# CESC16.net
KiCad netlist of a schematic drawn in EasyEDA
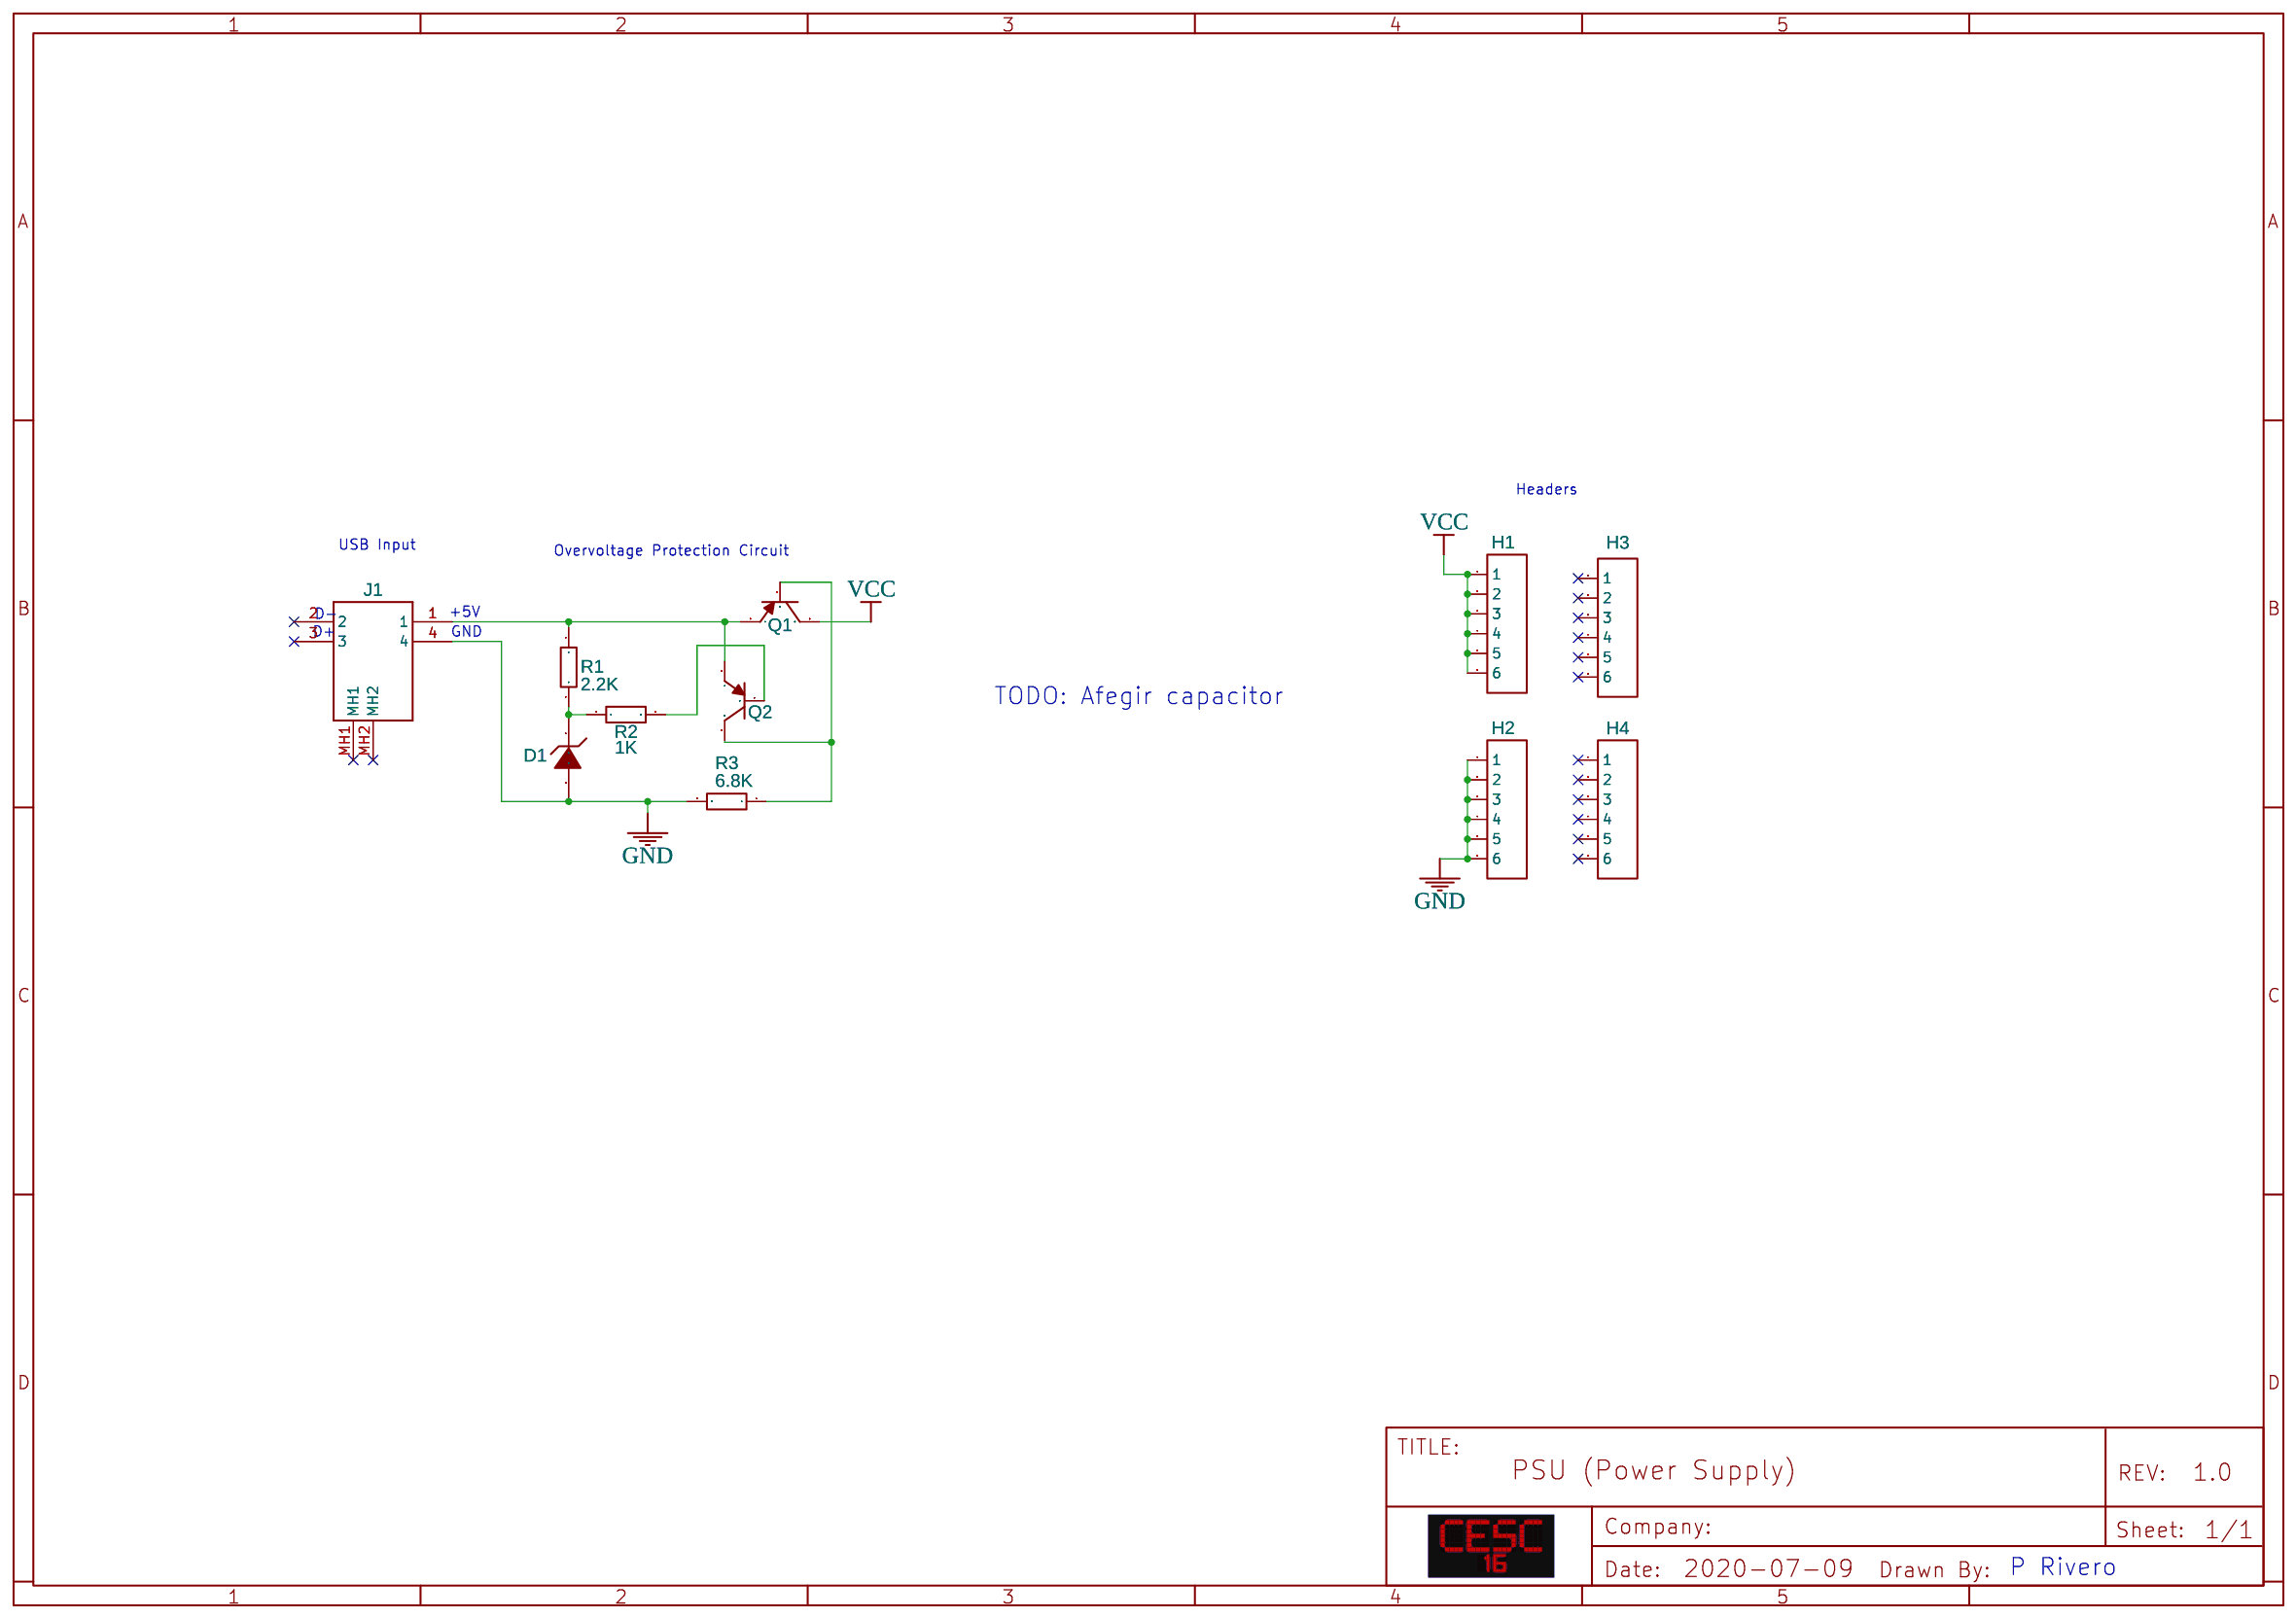
[diagram p0: PSU]
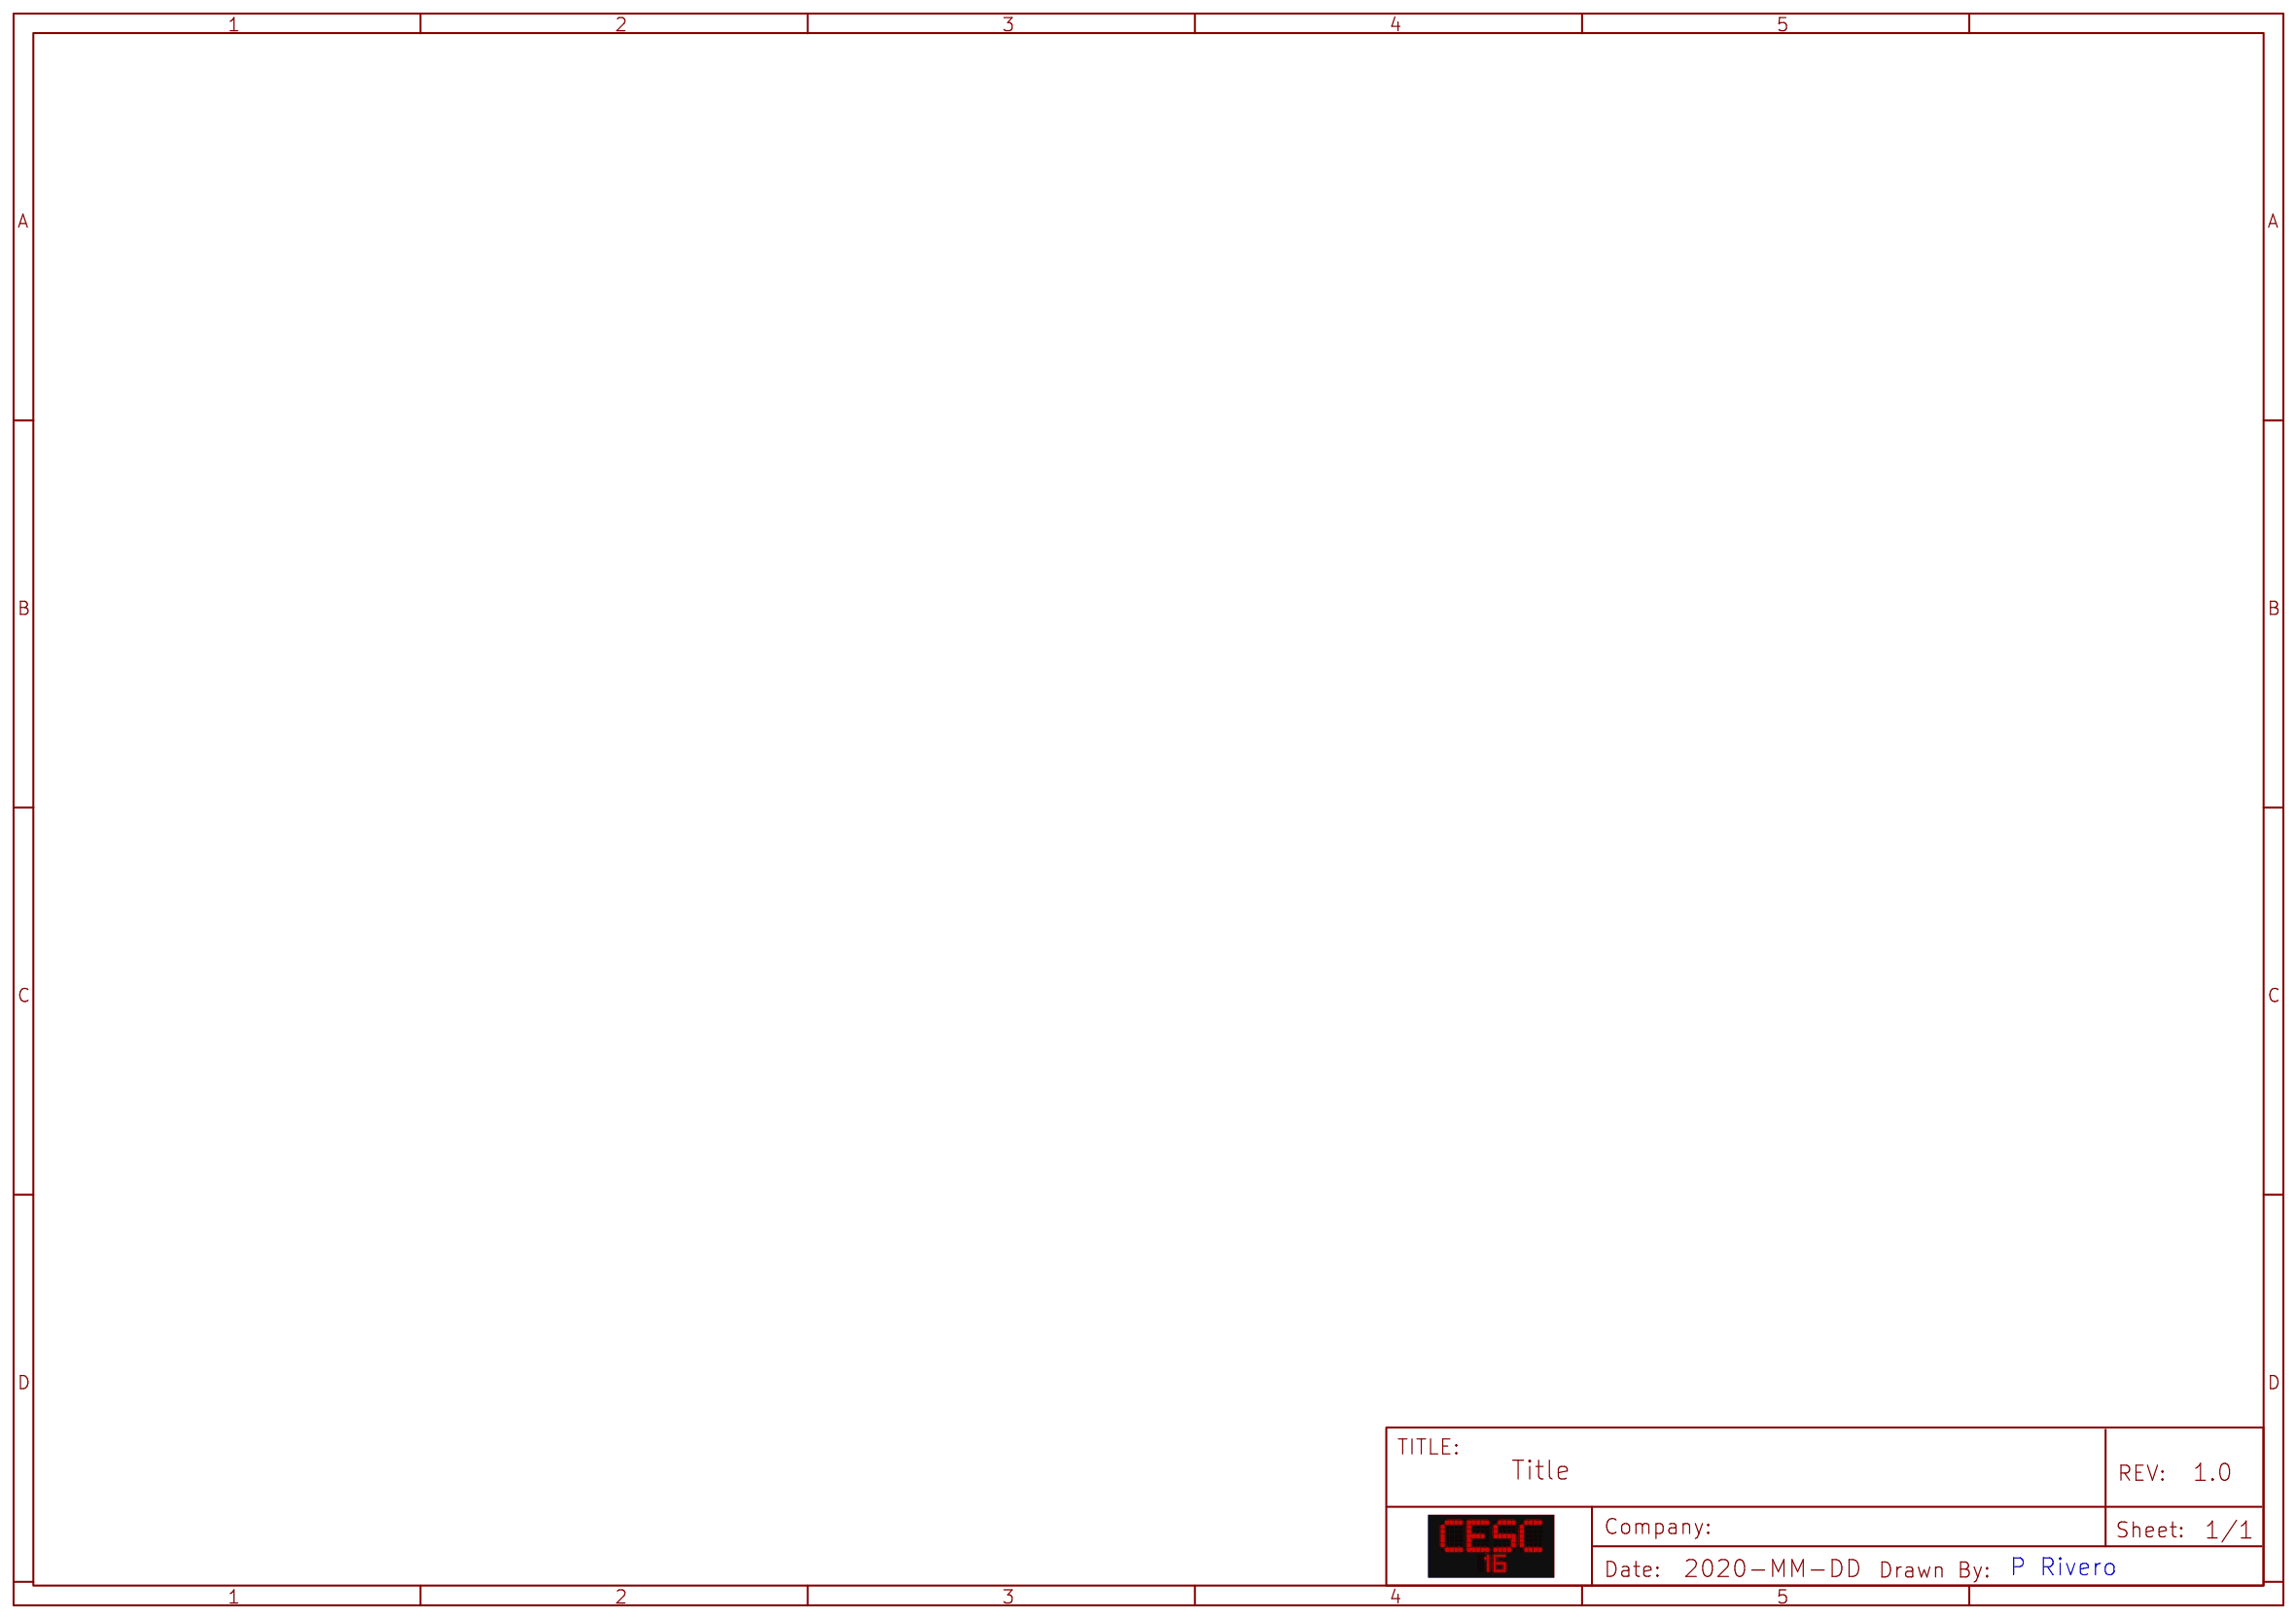
[diagram p1: _Template]
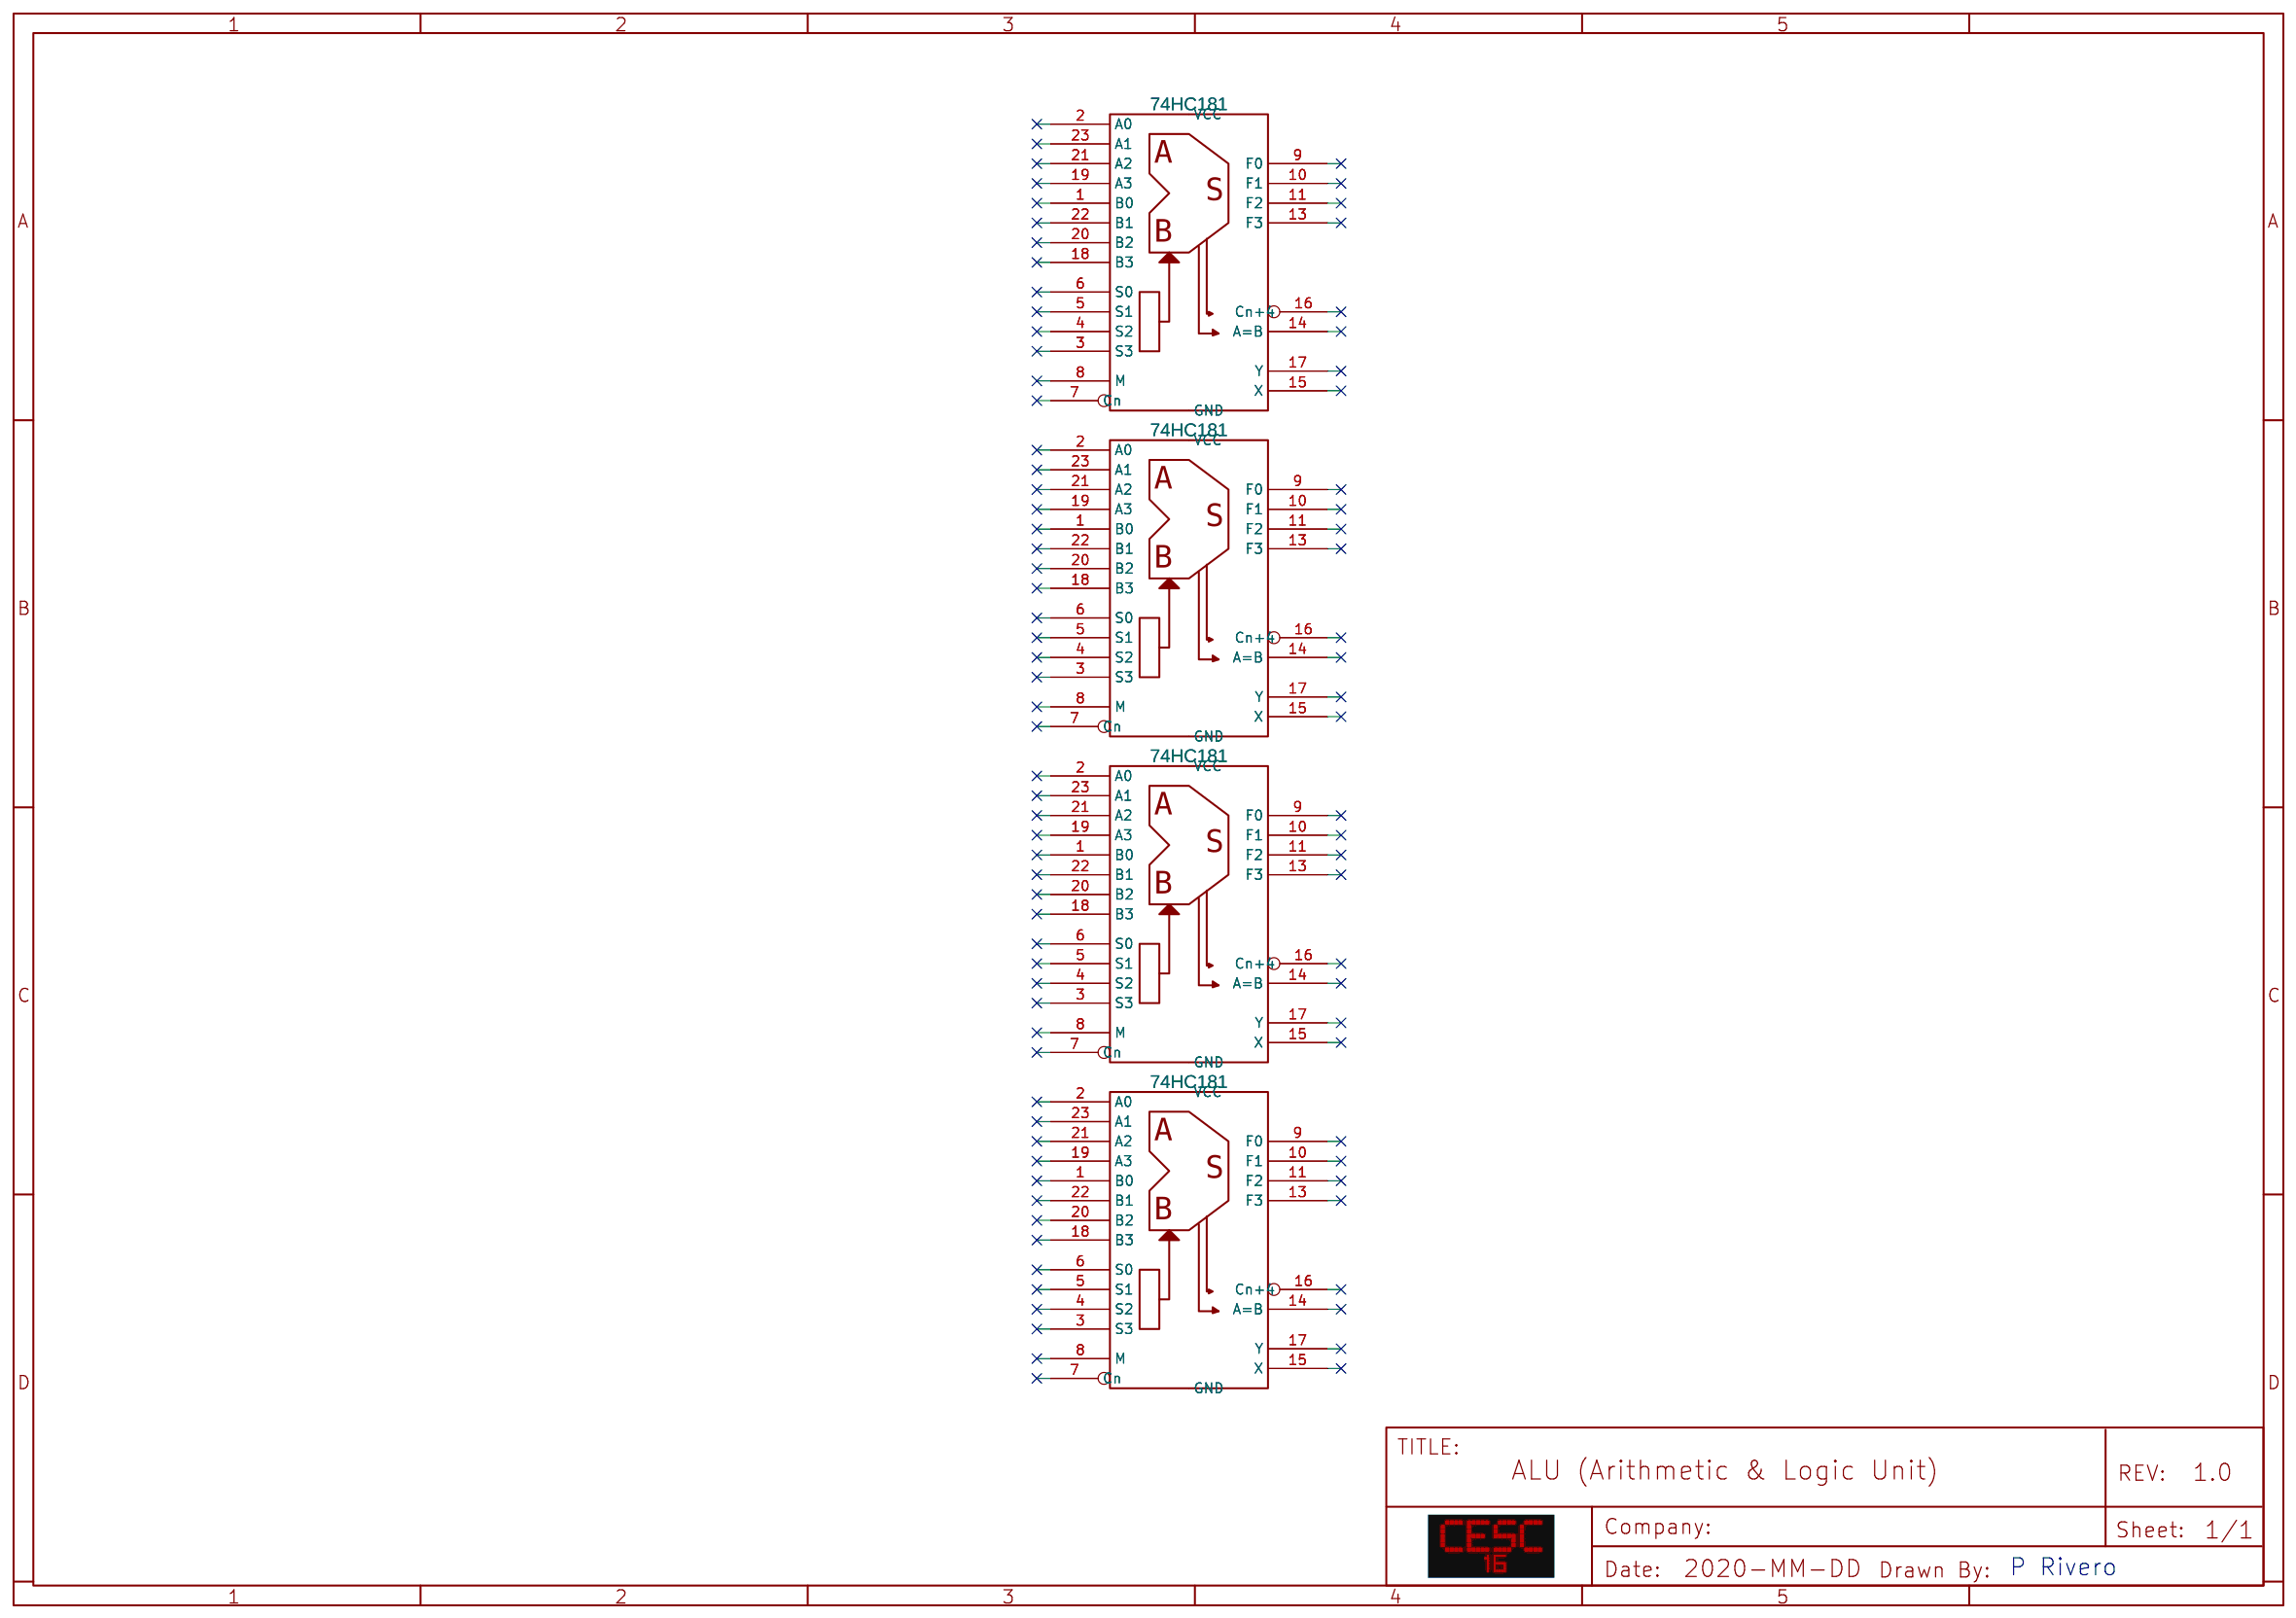
[diagram p2: ALU]
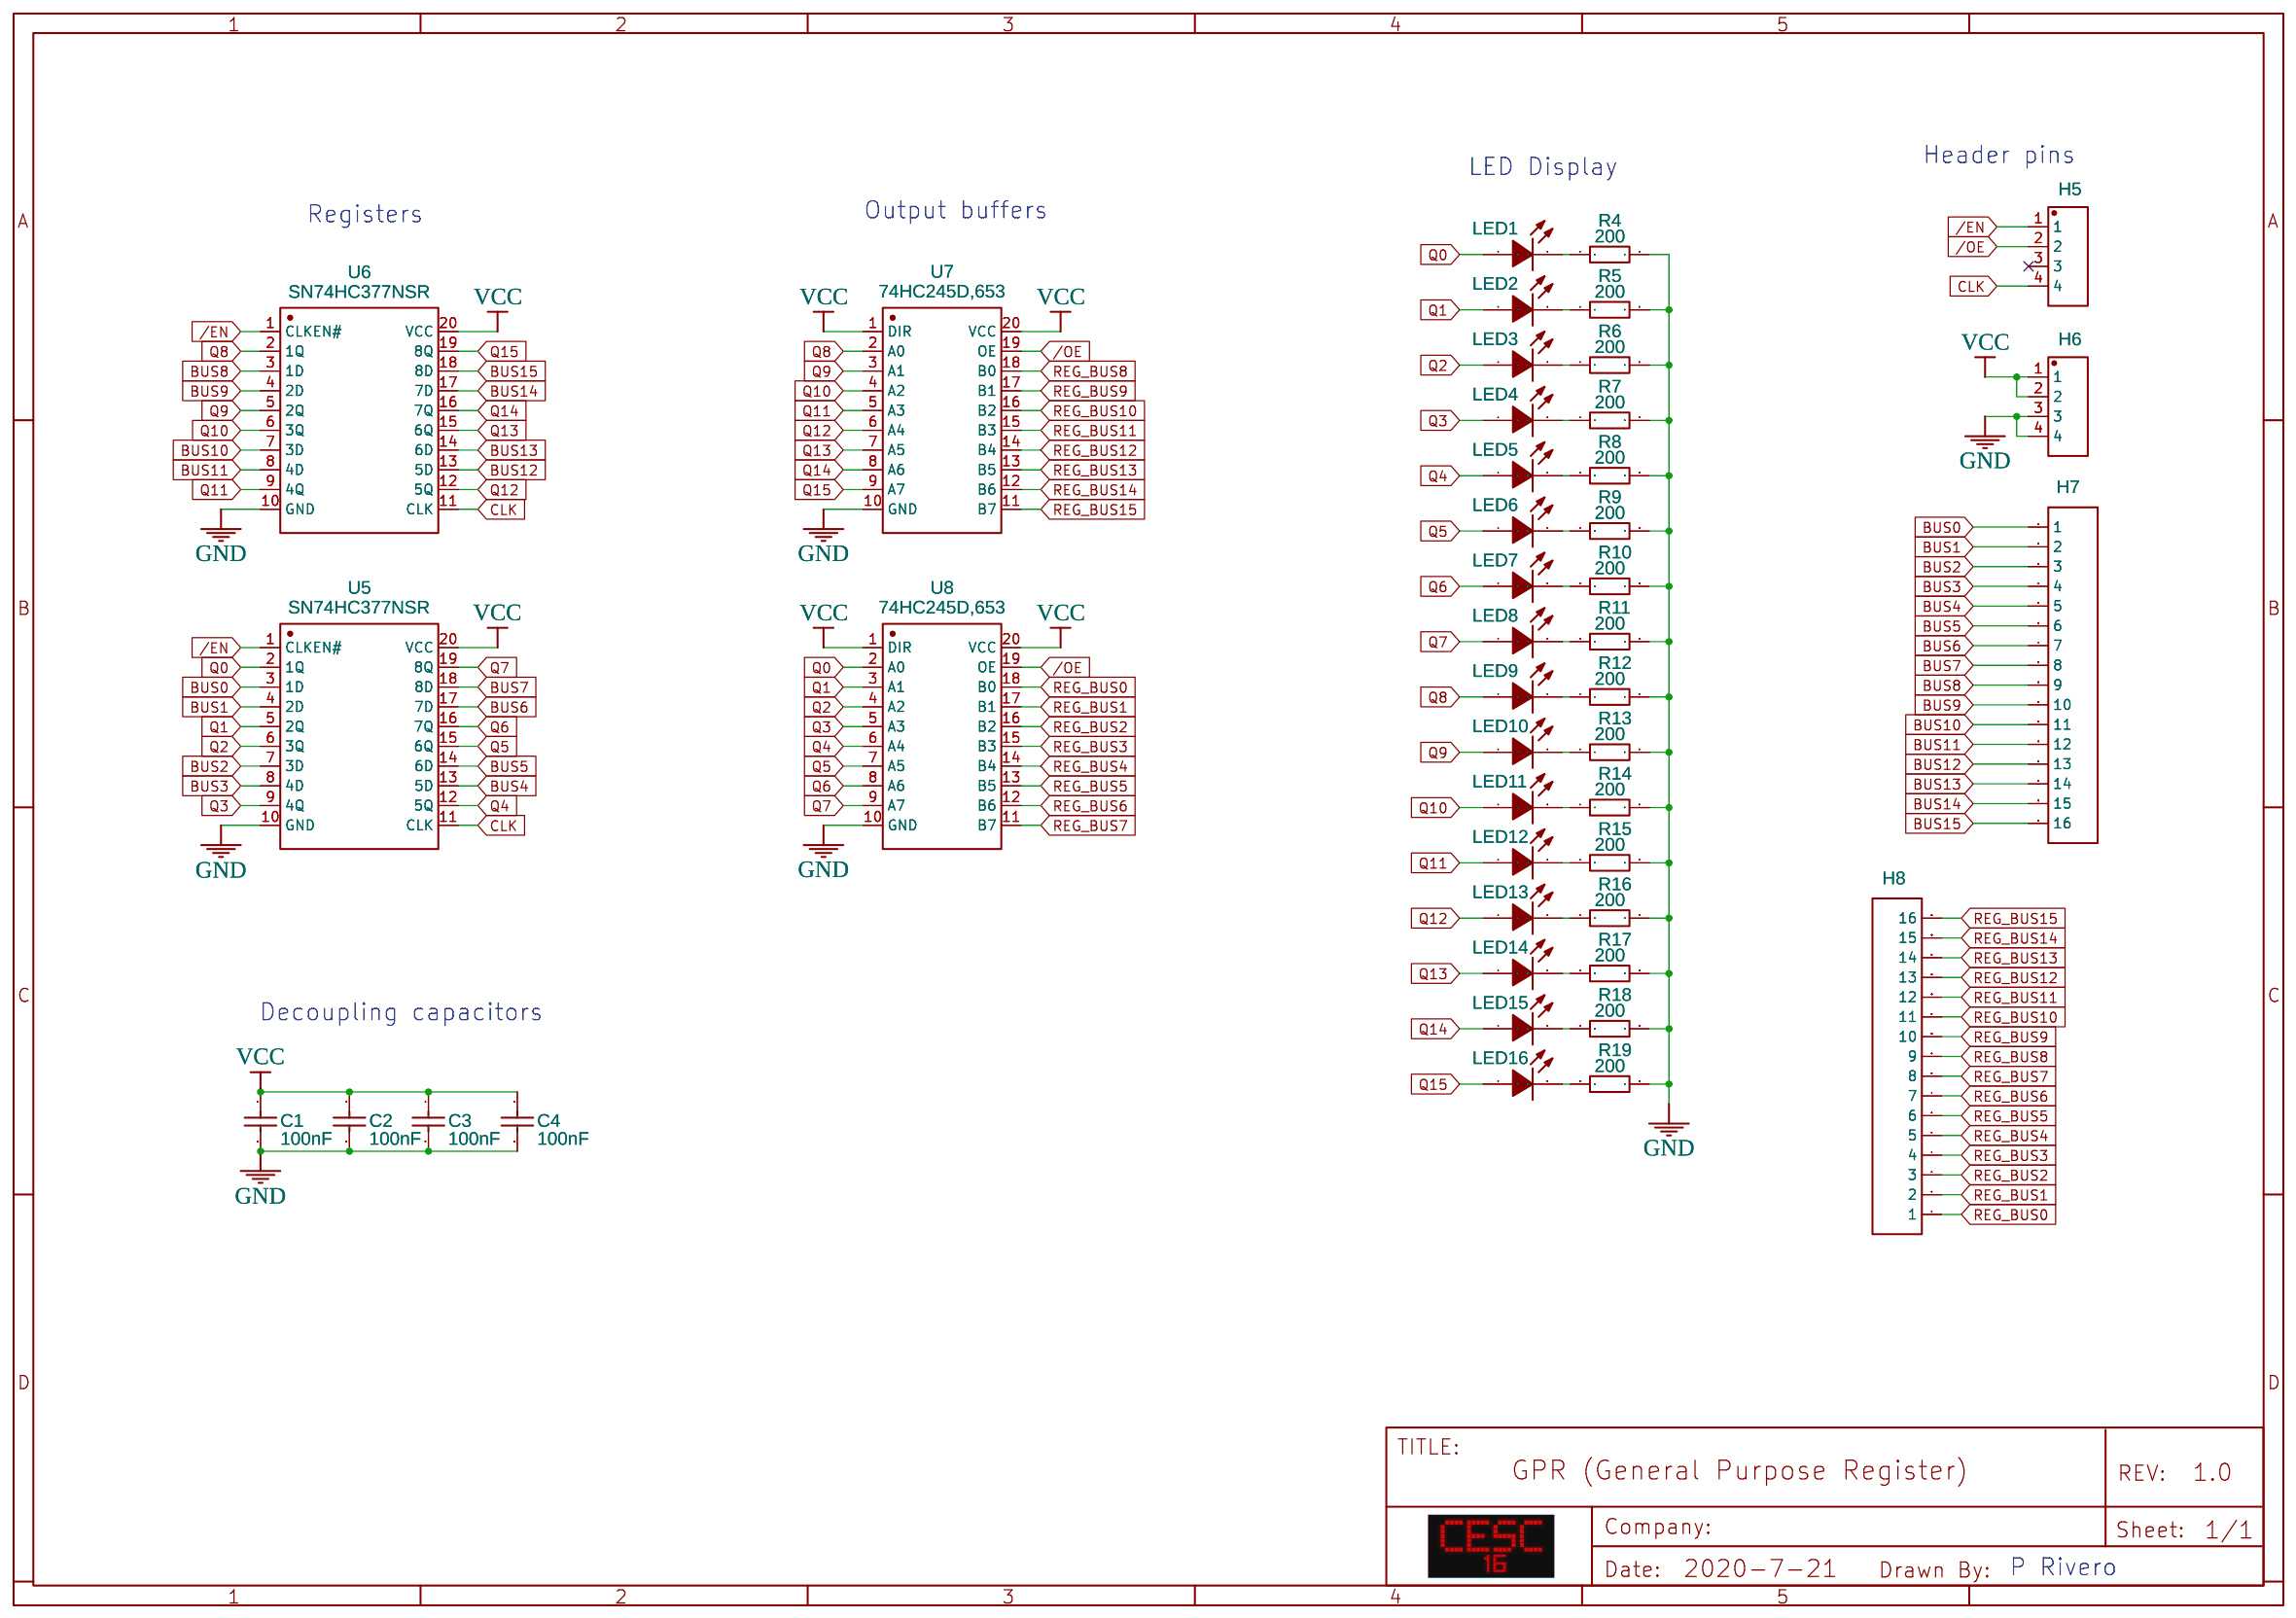
[diagram p3: GPR]

(export (version "E")
  (design (tool "Eeschema 10.0.6"))
  (components
    (comp (ref "D1")
      (value "ZMM5V6")
      (fields (field (name "BOM_Supplier Part") "C8062"))
      (libsource (lib "") (part "ZMM5V6"))
    )
    (comp (ref "H1")
      (value "Header-Male-2.54_1x6")
      (fields (field (name "BOM_Supplier Part") "C37208"))
      (libsource (lib "") (part "Header-Male-2.54_1x6"))
    )
    (comp (ref "H2")
      (value "Header-Male-2.54_1x6")
      (fields (field (name "BOM_Supplier Part") "C37208"))
      (libsource (lib "") (part "Header-Male-2.54_1x6"))
    )
    (comp (ref "H3")
      (value "Header-Male-2.54_1x6")
      (fields (field (name "BOM_Supplier Part") "C37208"))
      (libsource (lib "") (part "Header-Male-2.54_1x6"))
    )
    (comp (ref "H4")
      (value "Header-Male-2.54_1x6")
      (fields (field (name "BOM_Supplier Part") "C37208"))
      (libsource (lib "") (part "Header-Male-2.54_1x6"))
    )
    (comp (ref "J1") (value "UJ2-BH-1-TH") (libsource (lib "") (part "UJ2-BH-1-TH")))
    (comp (ref "Q1")
      (value "S9012 2T1")
      (fields (field (name "BOM_Supplier Part") "C8543"))
      (libsource (lib "") (part "S9012 2T1_1"))
    )
    (comp (ref "Q2")
      (value "S9012 2T1")
      (fields (field (name "BOM_Supplier Part") "C8543"))
      (libsource (lib "") (part "S9012 2T1"))
    )
    (comp (ref "R1")
      (value "2.2K")
      (fields
        (field (name "BOM_Manufacturer Part") "0603WAF2201T5E")
        (field (name "BOM_Supplier Part") "C4190")
      )
      (libsource (lib "") (part "0603WAF2201T5E"))
    )
    (comp (ref "R2")
      (value "1K")
      (fields
        (field (name "BOM_Manufacturer Part") "0402WGF1001TCE")
        (field (name "BOM_Supplier Part") "C11702")
      )
      (libsource (lib "") (part "0402WGF1001TCE"))
    )
    (comp (ref "R3")
      (value "6.8K")
      (fields
        (field (name "BOM_Manufacturer Part") "0402WGF6801TCE")
        (field (name "BOM_Supplier Part") "C25917")
      )
      (libsource (lib "") (part "0402WGF6801TCE"))
    )
    (comp (ref "U1") (value "74HC181") (libsource (lib "") (part "74LS181")))
    (comp (ref "U2") (value "74HC181") (libsource (lib "") (part "74LS181")))
    (comp (ref "U3") (value "74HC181") (libsource (lib "") (part "74LS181")))
    (comp (ref "U4") (value "74HC181") (libsource (lib "") (part "74LS181")))
    (comp (ref "C1")
      (value "100nF")
      (fields
        (field (name "BOM_Manufacturer Part") "CL05B104KO5NNNC")
        (field (name "BOM_Supplier Part") "C1525")
      )
      (libsource (lib "") (part "CL05B104KO5NNNC"))
    )
    (comp (ref "C2")
      (value "100nF")
      (fields
        (field (name "BOM_Manufacturer Part") "CL05B104KO5NNNC")
        (field (name "BOM_Supplier Part") "C1525")
      )
      (libsource (lib "") (part "CL05B104KO5NNNC"))
    )
    (comp (ref "C3")
      (value "100nF")
      (fields
        (field (name "BOM_Manufacturer Part") "CL05B104KO5NNNC")
        (field (name "BOM_Supplier Part") "C1525")
      )
      (libsource (lib "") (part "CL05B104KO5NNNC"))
    )
    (comp (ref "C4")
      (value "100nF")
      (fields
        (field (name "BOM_Manufacturer Part") "CL05B104KO5NNNC")
        (field (name "BOM_Supplier Part") "C1525")
      )
      (libsource (lib "") (part "CL05B104KO5NNNC"))
    )
    (comp (ref "H5")
      (value "Header-Male-2.54_1x4_C59481")
      (fields
        (field (name "BOM_Manufacturer Part") "Headers  Pins 1*4P")
        (field (name "BOM_Supplier Part") "C59481")
      )
      (libsource (lib "") (part "Header-Male-2.54_1x4_C59481"))
    )
    (comp (ref "H6")
      (value "Header-Male-2.54_1x4_C59481")
      (fields
        (field (name "BOM_Manufacturer Part") "Headers  Pins 1*4P")
        (field (name "BOM_Supplier Part") "C59481")
      )
      (libsource (lib "") (part "Header-Male-2.54_1x4_C59481"))
    )
    (comp (ref "H7")
      (value "Header-Female-2.54_1x16")
      (fields
        (field (name "BOM_Manufacturer Part") "Female header1*16P pitch 2.54mm")
        (field (name "BOM_Supplier Part") "C66987")
      )
      (libsource (lib "") (part "Header-Female-2.54_1x16_1"))
    )
    (comp (ref "H8")
      (value "Header-Female-2.54_1x16")
      (fields
        (field (name "BOM_Manufacturer Part") "Female header1*16P pitch 2.54mm")
        (field (name "BOM_Supplier Part") "C66987")
      )
      (libsource (lib "") (part "Header-Female-2.54_1x16"))
    )
    (comp (ref "LED1")
      (value "KT-0603R")
      (fields (field (name "BOM_Supplier Part") "C2286"))
      (libsource (lib "") (part "KT-0603R"))
    )
    (comp (ref "LED2")
      (value "KT-0603R")
      (fields (field (name "BOM_Supplier Part") "C2286"))
      (libsource (lib "") (part "KT-0603R"))
    )
    (comp (ref "LED3")
      (value "KT-0603R")
      (fields (field (name "BOM_Supplier Part") "C2286"))
      (libsource (lib "") (part "KT-0603R"))
    )
    (comp (ref "LED4")
      (value "KT-0603R")
      (fields (field (name "BOM_Supplier Part") "C2286"))
      (libsource (lib "") (part "KT-0603R"))
    )
    (comp (ref "LED5")
      (value "KT-0603R")
      (fields (field (name "BOM_Supplier Part") "C2286"))
      (libsource (lib "") (part "KT-0603R"))
    )
    (comp (ref "LED6")
      (value "KT-0603R")
      (fields (field (name "BOM_Supplier Part") "C2286"))
      (libsource (lib "") (part "KT-0603R"))
    )
    (comp (ref "LED7")
      (value "KT-0603R")
      (fields (field (name "BOM_Supplier Part") "C2286"))
      (libsource (lib "") (part "KT-0603R"))
    )
    (comp (ref "LED8")
      (value "KT-0603R")
      (fields (field (name "BOM_Supplier Part") "C2286"))
      (libsource (lib "") (part "KT-0603R"))
    )
    (comp (ref "LED9")
      (value "KT-0603R")
      (fields (field (name "BOM_Supplier Part") "C2286"))
      (libsource (lib "") (part "KT-0603R"))
    )
    (comp (ref "LED10")
      (value "KT-0603R")
      (fields (field (name "BOM_Supplier Part") "C2286"))
      (libsource (lib "") (part "KT-0603R"))
    )
    (comp (ref "LED11")
      (value "KT-0603R")
      (fields (field (name "BOM_Supplier Part") "C2286"))
      (libsource (lib "") (part "KT-0603R"))
    )
    (comp (ref "LED12")
      (value "KT-0603R")
      (fields (field (name "BOM_Supplier Part") "C2286"))
      (libsource (lib "") (part "KT-0603R"))
    )
    (comp (ref "LED13")
      (value "KT-0603R")
      (fields (field (name "BOM_Supplier Part") "C2286"))
      (libsource (lib "") (part "KT-0603R"))
    )
    (comp (ref "LED14")
      (value "KT-0603R")
      (fields (field (name "BOM_Supplier Part") "C2286"))
      (libsource (lib "") (part "KT-0603R"))
    )
    (comp (ref "LED15")
      (value "KT-0603R")
      (fields (field (name "BOM_Supplier Part") "C2286"))
      (libsource (lib "") (part "KT-0603R"))
    )
    (comp (ref "LED16")
      (value "KT-0603R")
      (fields (field (name "BOM_Supplier Part") "C2286"))
      (libsource (lib "") (part "KT-0603R"))
    )
    (comp (ref "R4")
      (value "200")
      (fields
        (field (name "BOM_Manufacturer Part") "0603WAF2000T5E")
        (field (name "BOM_Supplier Part") "C8218")
      )
      (libsource (lib "") (part "0603WAF2000T5E"))
    )
    (comp (ref "R5")
      (value "200")
      (fields
        (field (name "BOM_Manufacturer Part") "0603WAF2000T5E")
        (field (name "BOM_Supplier Part") "C8218")
      )
      (libsource (lib "") (part "0603WAF2000T5E"))
    )
    (comp (ref "R6")
      (value "200")
      (fields
        (field (name "BOM_Manufacturer Part") "0603WAF2000T5E")
        (field (name "BOM_Supplier Part") "C8218")
      )
      (libsource (lib "") (part "0603WAF2000T5E"))
    )
    (comp (ref "R7")
      (value "200")
      (fields
        (field (name "BOM_Manufacturer Part") "0603WAF2000T5E")
        (field (name "BOM_Supplier Part") "C8218")
      )
      (libsource (lib "") (part "0603WAF2000T5E"))
    )
    (comp (ref "R8")
      (value "200")
      (fields
        (field (name "BOM_Manufacturer Part") "0603WAF2000T5E")
        (field (name "BOM_Supplier Part") "C8218")
      )
      (libsource (lib "") (part "0603WAF2000T5E"))
    )
    (comp (ref "R9")
      (value "200")
      (fields
        (field (name "BOM_Manufacturer Part") "0603WAF2000T5E")
        (field (name "BOM_Supplier Part") "C8218")
      )
      (libsource (lib "") (part "0603WAF2000T5E"))
    )
    (comp (ref "R10")
      (value "200")
      (fields
        (field (name "BOM_Manufacturer Part") "0603WAF2000T5E")
        (field (name "BOM_Supplier Part") "C8218")
      )
      (libsource (lib "") (part "0603WAF2000T5E"))
    )
    (comp (ref "R11")
      (value "200")
      (fields
        (field (name "BOM_Manufacturer Part") "0603WAF2000T5E")
        (field (name "BOM_Supplier Part") "C8218")
      )
      (libsource (lib "") (part "0603WAF2000T5E"))
    )
    (comp (ref "R12")
      (value "200")
      (fields
        (field (name "BOM_Manufacturer Part") "0603WAF2000T5E")
        (field (name "BOM_Supplier Part") "C8218")
      )
      (libsource (lib "") (part "0603WAF2000T5E"))
    )
    (comp (ref "R13")
      (value "200")
      (fields
        (field (name "BOM_Manufacturer Part") "0603WAF2000T5E")
        (field (name "BOM_Supplier Part") "C8218")
      )
      (libsource (lib "") (part "0603WAF2000T5E"))
    )
    (comp (ref "R14")
      (value "200")
      (fields
        (field (name "BOM_Manufacturer Part") "0603WAF2000T5E")
        (field (name "BOM_Supplier Part") "C8218")
      )
      (libsource (lib "") (part "0603WAF2000T5E"))
    )
    (comp (ref "R15")
      (value "200")
      (fields
        (field (name "BOM_Manufacturer Part") "0603WAF2000T5E")
        (field (name "BOM_Supplier Part") "C8218")
      )
      (libsource (lib "") (part "0603WAF2000T5E"))
    )
    (comp (ref "R16")
      (value "200")
      (fields
        (field (name "BOM_Manufacturer Part") "0603WAF2000T5E")
        (field (name "BOM_Supplier Part") "C8218")
      )
      (libsource (lib "") (part "0603WAF2000T5E"))
    )
    (comp (ref "R17")
      (value "200")
      (fields
        (field (name "BOM_Manufacturer Part") "0603WAF2000T5E")
        (field (name "BOM_Supplier Part") "C8218")
      )
      (libsource (lib "") (part "0603WAF2000T5E"))
    )
    (comp (ref "R18")
      (value "200")
      (fields
        (field (name "BOM_Manufacturer Part") "0603WAF2000T5E")
        (field (name "BOM_Supplier Part") "C8218")
      )
      (libsource (lib "") (part "0603WAF2000T5E"))
    )
    (comp (ref "R19")
      (value "200")
      (fields
        (field (name "BOM_Manufacturer Part") "0603WAF2000T5E")
        (field (name "BOM_Supplier Part") "C8218")
      )
      (libsource (lib "") (part "0603WAF2000T5E"))
    )
    (comp (ref "U5")
      (value "SN74HC377NSR")
      (fields (field (name "BOM_Supplier Part") "C7647"))
      (libsource (lib "") (part "SN74HC377NSR"))
    )
    (comp (ref "U6")
      (value "SN74HC377NSR")
      (fields (field (name "BOM_Supplier Part") "C7647"))
      (libsource (lib "") (part "SN74HC377NSR"))
    )
    (comp (ref "U7")
      (value "74HC245D,653")
      (fields (field (name "BOM_Supplier Part") "C5625"))
      (libsource (lib "") (part "74HC245D,653"))
    )
    (comp (ref "U8")
      (value "74HC245D,653")
      (fields (field (name "BOM_Supplier Part") "C5625"))
      (libsource (lib "") (part "74HC245D,653"))
    )
  )
  (nets
    (net (code "1") (name "BUS0") (class "Default")
      (node (ref "H7") (pin "1") (pinfunction "1_1") (pintype "input"))
      (node (ref "U5") (pin "3") (pinfunction "1D_3") (pintype "unspecified"))
    )
    (net (code "2") (name "BUS1") (class "Default")
      (node (ref "H7") (pin "2") (pinfunction "2_2") (pintype "input"))
      (node (ref "U5") (pin "4") (pinfunction "2D_4") (pintype "unspecified"))
    )
    (net (code "3") (name "BUS2") (class "Default")
      (node (ref "H7") (pin "3") (pinfunction "3_3") (pintype "input"))
      (node (ref "U5") (pin "7") (pinfunction "3D_7") (pintype "unspecified"))
    )
    (net (code "4") (name "BUS3") (class "Default")
      (node (ref "H7") (pin "4") (pinfunction "4_4") (pintype "input"))
      (node (ref "U5") (pin "8") (pinfunction "4D_8") (pintype "unspecified"))
    )
    (net (code "5") (name "BUS4") (class "Default")
      (node (ref "H7") (pin "5") (pinfunction "5_5") (pintype "input"))
      (node (ref "U5") (pin "13") (pinfunction "5D_13") (pintype "unspecified"))
    )
    (net (code "6") (name "BUS5") (class "Default")
      (node (ref "H7") (pin "6") (pinfunction "6_6") (pintype "input"))
      (node (ref "U5") (pin "14") (pinfunction "6D_14") (pintype "unspecified"))
    )
    (net (code "7") (name "BUS6") (class "Default")
      (node (ref "H7") (pin "7") (pinfunction "7_7") (pintype "input"))
      (node (ref "U5") (pin "17") (pinfunction "7D_17") (pintype "unspecified"))
    )
    (net (code "8") (name "BUS7") (class "Default")
      (node (ref "H7") (pin "8") (pinfunction "8_8") (pintype "input"))
      (node (ref "U5") (pin "18") (pinfunction "8D_18") (pintype "unspecified"))
    )
    (net (code "9") (name "BUS8") (class "Default")
      (node (ref "H7") (pin "9") (pinfunction "9_9") (pintype "input"))
      (node (ref "U6") (pin "3") (pinfunction "1D_3") (pintype "unspecified"))
    )
    (net (code "10") (name "BUS9") (class "Default")
      (node (ref "H7") (pin "10") (pinfunction "10_10") (pintype "input"))
      (node (ref "U6") (pin "4") (pinfunction "2D_4") (pintype "unspecified"))
    )
    (net (code "11") (name "BUS10") (class "Default")
      (node (ref "H7") (pin "11") (pinfunction "11_11") (pintype "input"))
      (node (ref "U6") (pin "7") (pinfunction "3D_7") (pintype "unspecified"))
    )
    (net (code "12") (name "BUS11") (class "Default")
      (node (ref "H7") (pin "12") (pinfunction "12_12") (pintype "input"))
      (node (ref "U6") (pin "8") (pinfunction "4D_8") (pintype "unspecified"))
    )
    (net (code "13") (name "BUS12") (class "Default")
      (node (ref "H7") (pin "13") (pinfunction "13_13") (pintype "input"))
      (node (ref "U6") (pin "13") (pinfunction "5D_13") (pintype "unspecified"))
    )
    (net (code "14") (name "BUS13") (class "Default")
      (node (ref "H7") (pin "14") (pinfunction "14_14") (pintype "input"))
      (node (ref "U6") (pin "14") (pinfunction "6D_14") (pintype "unspecified"))
    )
    (net (code "15") (name "BUS14") (class "Default")
      (node (ref "H7") (pin "15") (pinfunction "15_15") (pintype "input"))
      (node (ref "U6") (pin "17") (pinfunction "7D_17") (pintype "unspecified"))
    )
    (net (code "16") (name "BUS15") (class "Default")
      (node (ref "H7") (pin "16") (pinfunction "16_16") (pintype "input"))
      (node (ref "U6") (pin "18") (pinfunction "8D_18") (pintype "unspecified"))
    )
    (net (code "17") (name "CLK") (class "Default")
      (node (ref "H5") (pin "4") (pinfunction "4_4") (pintype "unspecified"))
      (node (ref "U5") (pin "11") (pinfunction "CLK_11") (pintype "unspecified"))
      (node (ref "U6") (pin "11") (pinfunction "CLK_11") (pintype "unspecified"))
    )
    (net (code "18") (name "GND") (class "Default")
      (node (ref "C1") (pin "2") (pinfunction "2_2") (pintype "input"))
      (node (ref "C2") (pin "2") (pinfunction "2_2") (pintype "input"))
      (node (ref "C3") (pin "2") (pinfunction "2_2") (pintype "input"))
      (node (ref "C4") (pin "2") (pinfunction "2_2") (pintype "input"))
      (node (ref "D1") (pin "2") (pinfunction "A_2") (pintype "unspecified"))
      (node (ref "H2") (pin "1") (pinfunction "1_1") (pintype "input"))
      (node (ref "H2") (pin "2") (pinfunction "2_2") (pintype "input"))
      (node (ref "H2") (pin "3") (pinfunction "3_3") (pintype "input"))
      (node (ref "H2") (pin "4") (pinfunction "4_4") (pintype "input"))
      (node (ref "H2") (pin "5") (pinfunction "5_5") (pintype "input"))
      (node (ref "H2") (pin "6") (pinfunction "6_6") (pintype "input"))
      (node (ref "H6") (pin "3") (pinfunction "3_3") (pintype "unspecified"))
      (node (ref "H6") (pin "4") (pinfunction "4_4") (pintype "unspecified"))
      (node (ref "J1") (pin "4") (pinfunction "4_4") (pintype "bidirectional"))
      (node (ref "R10") (pin "2") (pinfunction "2_2") (pintype "input"))
      (node (ref "R11") (pin "2") (pinfunction "2_2") (pintype "input"))
      (node (ref "R12") (pin "2") (pinfunction "2_2") (pintype "input"))
      (node (ref "R13") (pin "2") (pinfunction "2_2") (pintype "input"))
      (node (ref "R14") (pin "2") (pinfunction "2_2") (pintype "input"))
      (node (ref "R15") (pin "2") (pinfunction "2_2") (pintype "input"))
      (node (ref "R16") (pin "2") (pinfunction "2_2") (pintype "input"))
      (node (ref "R17") (pin "2") (pinfunction "2_2") (pintype "input"))
      (node (ref "R18") (pin "2") (pinfunction "2_2") (pintype "input"))
      (node (ref "R19") (pin "2") (pinfunction "2_2") (pintype "input"))
      (node (ref "R3") (pin "2") (pinfunction "2_2") (pintype "input"))
      (node (ref "R4") (pin "2") (pinfunction "2_2") (pintype "input"))
      (node (ref "R5") (pin "2") (pinfunction "2_2") (pintype "input"))
      (node (ref "R6") (pin "2") (pinfunction "2_2") (pintype "input"))
      (node (ref "R7") (pin "2") (pinfunction "2_2") (pintype "input"))
      (node (ref "R8") (pin "2") (pinfunction "2_2") (pintype "input"))
      (node (ref "R9") (pin "2") (pinfunction "2_2") (pintype "input"))
      (node (ref "U5") (pin "10") (pinfunction "GND_10") (pintype "unspecified"))
      (node (ref "U6") (pin "10") (pinfunction "GND_10") (pintype "unspecified"))
      (node (ref "U7") (pin "10") (pinfunction "GND_10") (pintype "unspecified"))
      (node (ref "U8") (pin "10") (pinfunction "GND_10") (pintype "unspecified"))
    )
    (net (code "19") (name "Net-(D1-C)") (class "Default")
      (node (ref "D1") (pin "1") (pinfunction "C_1") (pintype "unspecified"))
      (node (ref "R1") (pin "2") (pinfunction "2_2") (pintype "input"))
      (node (ref "R2") (pin "1") (pinfunction "1_1") (pintype "input"))
    )
    (net (code "20") (name "Net-(LED1-K)") (class "Default")
      (node (ref "LED1") (pin "2") (pinfunction "K_2") (pintype "unspecified"))
      (node (ref "R4") (pin "1") (pinfunction "1_1") (pintype "input"))
    )
    (net (code "21") (name "Net-(LED2-K)") (class "Default")
      (node (ref "LED2") (pin "2") (pinfunction "K_2") (pintype "unspecified"))
      (node (ref "R5") (pin "1") (pinfunction "1_1") (pintype "input"))
    )
    (net (code "22") (name "Net-(LED3-K)") (class "Default")
      (node (ref "LED3") (pin "2") (pinfunction "K_2") (pintype "unspecified"))
      (node (ref "R6") (pin "1") (pinfunction "1_1") (pintype "input"))
    )
    (net (code "23") (name "Net-(LED4-K)") (class "Default")
      (node (ref "LED4") (pin "2") (pinfunction "K_2") (pintype "unspecified"))
      (node (ref "R7") (pin "1") (pinfunction "1_1") (pintype "input"))
    )
    (net (code "24") (name "Net-(LED5-K)") (class "Default")
      (node (ref "LED5") (pin "2") (pinfunction "K_2") (pintype "unspecified"))
      (node (ref "R8") (pin "1") (pinfunction "1_1") (pintype "input"))
    )
    (net (code "25") (name "Net-(LED6-K)") (class "Default")
      (node (ref "LED6") (pin "2") (pinfunction "K_2") (pintype "unspecified"))
      (node (ref "R9") (pin "1") (pinfunction "1_1") (pintype "input"))
    )
    (net (code "26") (name "Net-(LED7-K)") (class "Default")
      (node (ref "LED7") (pin "2") (pinfunction "K_2") (pintype "unspecified"))
      (node (ref "R10") (pin "1") (pinfunction "1_1") (pintype "input"))
    )
    (net (code "27") (name "Net-(LED8-K)") (class "Default")
      (node (ref "LED8") (pin "2") (pinfunction "K_2") (pintype "unspecified"))
      (node (ref "R11") (pin "1") (pinfunction "1_1") (pintype "input"))
    )
    (net (code "28") (name "Net-(LED9-K)") (class "Default")
      (node (ref "LED9") (pin "2") (pinfunction "K_2") (pintype "unspecified"))
      (node (ref "R12") (pin "1") (pinfunction "1_1") (pintype "input"))
    )
    (net (code "29") (name "Net-(LED10-K)") (class "Default")
      (node (ref "LED10") (pin "2") (pinfunction "K_2") (pintype "unspecified"))
      (node (ref "R13") (pin "1") (pinfunction "1_1") (pintype "input"))
    )
    (net (code "30") (name "Net-(LED11-K)") (class "Default")
      (node (ref "LED11") (pin "2") (pinfunction "K_2") (pintype "unspecified"))
      (node (ref "R14") (pin "1") (pinfunction "1_1") (pintype "input"))
    )
    (net (code "31") (name "Net-(LED12-K)") (class "Default")
      (node (ref "LED12") (pin "2") (pinfunction "K_2") (pintype "unspecified"))
      (node (ref "R15") (pin "1") (pinfunction "1_1") (pintype "input"))
    )
    (net (code "32") (name "Net-(LED13-K)") (class "Default")
      (node (ref "LED13") (pin "2") (pinfunction "K_2") (pintype "unspecified"))
      (node (ref "R16") (pin "1") (pinfunction "1_1") (pintype "input"))
    )
    (net (code "33") (name "Net-(LED14-K)") (class "Default")
      (node (ref "LED14") (pin "2") (pinfunction "K_2") (pintype "unspecified"))
      (node (ref "R17") (pin "1") (pinfunction "1_1") (pintype "input"))
    )
    (net (code "34") (name "Net-(LED15-K)") (class "Default")
      (node (ref "LED15") (pin "2") (pinfunction "K_2") (pintype "unspecified"))
      (node (ref "R18") (pin "1") (pinfunction "1_1") (pintype "input"))
    )
    (net (code "35") (name "Net-(LED16-K)") (class "Default")
      (node (ref "LED16") (pin "2") (pinfunction "K_2") (pintype "unspecified"))
      (node (ref "R19") (pin "1") (pinfunction "1_1") (pintype "input"))
    )
    (net (code "36") (name "Net-(Q1-B)") (class "Default")
      (node (ref "Q1") (pin "1") (pinfunction "B_1") (pintype "unspecified"))
      (node (ref "Q2") (pin "3") (pinfunction "C_3") (pintype "unspecified"))
      (node (ref "R3") (pin "1") (pinfunction "1_1") (pintype "input"))
    )
    (net (code "37") (name "Net-(Q1-E)") (class "Default")
      (node (ref "J1") (pin "1") (pinfunction "1_1") (pintype "bidirectional"))
      (node (ref "Q1") (pin "2") (pinfunction "E_2") (pintype "unspecified"))
      (node (ref "Q2") (pin "2") (pinfunction "E_2") (pintype "unspecified"))
      (node (ref "R1") (pin "1") (pinfunction "1_1") (pintype "input"))
    )
    (net (code "38") (name "Net-(Q2-B)") (class "Default")
      (node (ref "Q2") (pin "1") (pinfunction "B_1") (pintype "unspecified"))
      (node (ref "R2") (pin "2") (pinfunction "2_2") (pintype "input"))
    )
    (net (code "39") (name "Q0") (class "Default")
      (node (ref "LED1") (pin "1") (pinfunction "A_1") (pintype "unspecified"))
      (node (ref "U5") (pin "2") (pinfunction "1Q_2") (pintype "unspecified"))
      (node (ref "U8") (pin "2") (pinfunction "A0_2") (pintype "unspecified"))
    )
    (net (code "40") (name "Q1") (class "Default")
      (node (ref "LED2") (pin "1") (pinfunction "A_1") (pintype "unspecified"))
      (node (ref "U5") (pin "5") (pinfunction "2Q_5") (pintype "unspecified"))
      (node (ref "U8") (pin "3") (pinfunction "A1_3") (pintype "unspecified"))
    )
    (net (code "41") (name "Q2") (class "Default")
      (node (ref "LED3") (pin "1") (pinfunction "A_1") (pintype "unspecified"))
      (node (ref "U5") (pin "6") (pinfunction "3Q_6") (pintype "unspecified"))
      (node (ref "U8") (pin "4") (pinfunction "A2_4") (pintype "unspecified"))
    )
    (net (code "42") (name "Q3") (class "Default")
      (node (ref "LED4") (pin "1") (pinfunction "A_1") (pintype "unspecified"))
      (node (ref "U5") (pin "9") (pinfunction "4Q_9") (pintype "unspecified"))
      (node (ref "U8") (pin "5") (pinfunction "A3_5") (pintype "unspecified"))
    )
    (net (code "43") (name "Q4") (class "Default")
      (node (ref "LED5") (pin "1") (pinfunction "A_1") (pintype "unspecified"))
      (node (ref "U5") (pin "12") (pinfunction "5Q_12") (pintype "unspecified"))
      (node (ref "U8") (pin "6") (pinfunction "A4_6") (pintype "unspecified"))
    )
    (net (code "44") (name "Q5") (class "Default")
      (node (ref "LED6") (pin "1") (pinfunction "A_1") (pintype "unspecified"))
      (node (ref "U5") (pin "15") (pinfunction "6Q_15") (pintype "unspecified"))
      (node (ref "U8") (pin "7") (pinfunction "A5_7") (pintype "unspecified"))
    )
    (net (code "45") (name "Q6") (class "Default")
      (node (ref "LED7") (pin "1") (pinfunction "A_1") (pintype "unspecified"))
      (node (ref "U5") (pin "16") (pinfunction "7Q_16") (pintype "unspecified"))
      (node (ref "U8") (pin "8") (pinfunction "A6_8") (pintype "unspecified"))
    )
    (net (code "46") (name "Q7") (class "Default")
      (node (ref "LED8") (pin "1") (pinfunction "A_1") (pintype "unspecified"))
      (node (ref "U5") (pin "19") (pinfunction "8Q_19") (pintype "unspecified"))
      (node (ref "U8") (pin "9") (pinfunction "A7_9") (pintype "unspecified"))
    )
    (net (code "47") (name "Q8") (class "Default")
      (node (ref "LED9") (pin "1") (pinfunction "A_1") (pintype "unspecified"))
      (node (ref "U6") (pin "2") (pinfunction "1Q_2") (pintype "unspecified"))
      (node (ref "U7") (pin "2") (pinfunction "A0_2") (pintype "unspecified"))
    )
    (net (code "48") (name "Q9") (class "Default")
      (node (ref "LED10") (pin "1") (pinfunction "A_1") (pintype "unspecified"))
      (node (ref "U6") (pin "5") (pinfunction "2Q_5") (pintype "unspecified"))
      (node (ref "U7") (pin "3") (pinfunction "A1_3") (pintype "unspecified"))
    )
    (net (code "49") (name "Q10") (class "Default")
      (node (ref "LED11") (pin "1") (pinfunction "A_1") (pintype "unspecified"))
      (node (ref "U6") (pin "6") (pinfunction "3Q_6") (pintype "unspecified"))
      (node (ref "U7") (pin "4") (pinfunction "A2_4") (pintype "unspecified"))
    )
    (net (code "50") (name "Q11") (class "Default")
      (node (ref "LED12") (pin "1") (pinfunction "A_1") (pintype "unspecified"))
      (node (ref "U6") (pin "9") (pinfunction "4Q_9") (pintype "unspecified"))
      (node (ref "U7") (pin "5") (pinfunction "A3_5") (pintype "unspecified"))
    )
    (net (code "51") (name "Q12") (class "Default")
      (node (ref "LED13") (pin "1") (pinfunction "A_1") (pintype "unspecified"))
      (node (ref "U6") (pin "12") (pinfunction "5Q_12") (pintype "unspecified"))
      (node (ref "U7") (pin "6") (pinfunction "A4_6") (pintype "unspecified"))
    )
    (net (code "52") (name "Q13") (class "Default")
      (node (ref "LED14") (pin "1") (pinfunction "A_1") (pintype "unspecified"))
      (node (ref "U6") (pin "15") (pinfunction "6Q_15") (pintype "unspecified"))
      (node (ref "U7") (pin "7") (pinfunction "A5_7") (pintype "unspecified"))
    )
    (net (code "53") (name "Q14") (class "Default")
      (node (ref "LED15") (pin "1") (pinfunction "A_1") (pintype "unspecified"))
      (node (ref "U6") (pin "16") (pinfunction "7Q_16") (pintype "unspecified"))
      (node (ref "U7") (pin "8") (pinfunction "A6_8") (pintype "unspecified"))
    )
    (net (code "54") (name "Q15") (class "Default")
      (node (ref "LED16") (pin "1") (pinfunction "A_1") (pintype "unspecified"))
      (node (ref "U6") (pin "19") (pinfunction "8Q_19") (pintype "unspecified"))
      (node (ref "U7") (pin "9") (pinfunction "A7_9") (pintype "unspecified"))
    )
    (net (code "55") (name "REG_BUS0") (class "Default")
      (node (ref "H8") (pin "1") (pinfunction "1_1") (pintype "input"))
      (node (ref "U8") (pin "18") (pinfunction "B0_18") (pintype "unspecified"))
    )
    (net (code "56") (name "REG_BUS1") (class "Default")
      (node (ref "H8") (pin "2") (pinfunction "2_2") (pintype "input"))
      (node (ref "U8") (pin "17") (pinfunction "B1_17") (pintype "unspecified"))
    )
    (net (code "57") (name "REG_BUS2") (class "Default")
      (node (ref "H8") (pin "3") (pinfunction "3_3") (pintype "input"))
      (node (ref "U8") (pin "16") (pinfunction "B2_16") (pintype "unspecified"))
    )
    (net (code "58") (name "REG_BUS3") (class "Default")
      (node (ref "H8") (pin "4") (pinfunction "4_4") (pintype "input"))
      (node (ref "U8") (pin "15") (pinfunction "B3_15") (pintype "unspecified"))
    )
    (net (code "59") (name "REG_BUS4") (class "Default")
      (node (ref "H8") (pin "5") (pinfunction "5_5") (pintype "input"))
      (node (ref "U8") (pin "14") (pinfunction "B4_14") (pintype "unspecified"))
    )
    (net (code "60") (name "REG_BUS5") (class "Default")
      (node (ref "H8") (pin "6") (pinfunction "6_6") (pintype "input"))
      (node (ref "U8") (pin "13") (pinfunction "B5_13") (pintype "unspecified"))
    )
    (net (code "61") (name "REG_BUS6") (class "Default")
      (node (ref "H8") (pin "7") (pinfunction "7_7") (pintype "input"))
      (node (ref "U8") (pin "12") (pinfunction "B6_12") (pintype "unspecified"))
    )
    (net (code "62") (name "REG_BUS7") (class "Default")
      (node (ref "H8") (pin "8") (pinfunction "8_8") (pintype "input"))
      (node (ref "U8") (pin "11") (pinfunction "B7_11") (pintype "unspecified"))
    )
    (net (code "63") (name "REG_BUS8") (class "Default")
      (node (ref "H8") (pin "9") (pinfunction "9_9") (pintype "input"))
      (node (ref "U7") (pin "18") (pinfunction "B0_18") (pintype "unspecified"))
    )
    (net (code "64") (name "REG_BUS9") (class "Default")
      (node (ref "H8") (pin "10") (pinfunction "10_10") (pintype "input"))
      (node (ref "U7") (pin "17") (pinfunction "B1_17") (pintype "unspecified"))
    )
    (net (code "65") (name "REG_BUS10") (class "Default")
      (node (ref "H8") (pin "11") (pinfunction "11_11") (pintype "input"))
      (node (ref "U7") (pin "16") (pinfunction "B2_16") (pintype "unspecified"))
    )
    (net (code "66") (name "REG_BUS11") (class "Default")
      (node (ref "H8") (pin "12") (pinfunction "12_12") (pintype "input"))
      (node (ref "U7") (pin "15") (pinfunction "B3_15") (pintype "unspecified"))
    )
    (net (code "67") (name "REG_BUS12") (class "Default")
      (node (ref "H8") (pin "13") (pinfunction "13_13") (pintype "input"))
      (node (ref "U7") (pin "14") (pinfunction "B4_14") (pintype "unspecified"))
    )
    (net (code "68") (name "REG_BUS13") (class "Default")
      (node (ref "H8") (pin "14") (pinfunction "14_14") (pintype "input"))
      (node (ref "U7") (pin "13") (pinfunction "B5_13") (pintype "unspecified"))
    )
    (net (code "69") (name "REG_BUS14") (class "Default")
      (node (ref "H8") (pin "15") (pinfunction "15_15") (pintype "input"))
      (node (ref "U7") (pin "12") (pinfunction "B6_12") (pintype "unspecified"))
    )
    (net (code "70") (name "REG_BUS15") (class "Default")
      (node (ref "H8") (pin "16") (pinfunction "16_16") (pintype "input"))
      (node (ref "U7") (pin "11") (pinfunction "B7_11") (pintype "unspecified"))
    )
    (net (code "71") (name "VCC") (class "Default")
      (node (ref "C1") (pin "1") (pinfunction "1_1") (pintype "input"))
      (node (ref "C2") (pin "1") (pinfunction "1_1") (pintype "input"))
      (node (ref "C3") (pin "1") (pinfunction "1_1") (pintype "input"))
      (node (ref "C4") (pin "1") (pinfunction "1_1") (pintype "input"))
      (node (ref "H1") (pin "1") (pinfunction "1_1") (pintype "input"))
      (node (ref "H1") (pin "2") (pinfunction "2_2") (pintype "input"))
      (node (ref "H1") (pin "3") (pinfunction "3_3") (pintype "input"))
      (node (ref "H1") (pin "4") (pinfunction "4_4") (pintype "input"))
      (node (ref "H1") (pin "5") (pinfunction "5_5") (pintype "input"))
      (node (ref "H1") (pin "6") (pinfunction "6_6") (pintype "input"))
      (node (ref "H6") (pin "1") (pinfunction "1_1") (pintype "unspecified"))
      (node (ref "H6") (pin "2") (pinfunction "2_2") (pintype "unspecified"))
      (node (ref "Q1") (pin "3") (pinfunction "C_3") (pintype "unspecified"))
      (node (ref "U5") (pin "20") (pinfunction "VCC_20") (pintype "unspecified"))
      (node (ref "U6") (pin "20") (pinfunction "VCC_20") (pintype "unspecified"))
      (node (ref "U7") (pin "1") (pinfunction "DIR_1") (pintype "unspecified"))
      (node (ref "U7") (pin "20") (pinfunction "VCC_20") (pintype "unspecified"))
      (node (ref "U8") (pin "1") (pinfunction "DIR_1") (pintype "unspecified"))
      (node (ref "U8") (pin "20") (pinfunction "VCC_20") (pintype "unspecified"))
    )
    (net (code "72") (name "unconnected-(H3-Pad1)") (class "Default")
      (node (ref "H3") (pin "1") (pinfunction "1_1") (pintype "input+no_connect"))
    )
    (net (code "73") (name "unconnected-(H3-Pad2)") (class "Default")
      (node (ref "H3") (pin "2") (pinfunction "2_2") (pintype "input+no_connect"))
    )
    (net (code "74") (name "unconnected-(H3-Pad3)") (class "Default")
      (node (ref "H3") (pin "3") (pinfunction "3_3") (pintype "input+no_connect"))
    )
    (net (code "75") (name "unconnected-(H3-Pad4)") (class "Default")
      (node (ref "H3") (pin "4") (pinfunction "4_4") (pintype "input+no_connect"))
    )
    (net (code "76") (name "unconnected-(H3-Pad5)") (class "Default")
      (node (ref "H3") (pin "5") (pinfunction "5_5") (pintype "input+no_connect"))
    )
    (net (code "77") (name "unconnected-(H3-Pad6)") (class "Default")
      (node (ref "H3") (pin "6") (pinfunction "6_6") (pintype "input+no_connect"))
    )
    (net (code "78") (name "unconnected-(H4-Pad1)") (class "Default")
      (node (ref "H4") (pin "1") (pinfunction "1_1") (pintype "input+no_connect"))
    )
    (net (code "79") (name "unconnected-(H4-Pad2)") (class "Default")
      (node (ref "H4") (pin "2") (pinfunction "2_2") (pintype "input+no_connect"))
    )
    (net (code "80") (name "unconnected-(H4-Pad3)") (class "Default")
      (node (ref "H4") (pin "3") (pinfunction "3_3") (pintype "input+no_connect"))
    )
    (net (code "81") (name "unconnected-(H4-Pad4)") (class "Default")
      (node (ref "H4") (pin "4") (pinfunction "4_4") (pintype "input+no_connect"))
    )
    (net (code "82") (name "unconnected-(H4-Pad5)") (class "Default")
      (node (ref "H4") (pin "5") (pinfunction "5_5") (pintype "input+no_connect"))
    )
    (net (code "83") (name "unconnected-(H4-Pad6)") (class "Default")
      (node (ref "H4") (pin "6") (pinfunction "6_6") (pintype "input+no_connect"))
    )
    (net (code "84") (name "unconnected-(H5-Pad3)") (class "Default")
      (node (ref "H5") (pin "3") (pinfunction "3_3") (pintype "unspecified+no_connect"))
    )
    (net (code "85") (name "unconnected-(J1-Pad2)") (class "Default")
      (node (ref "J1") (pin "2") (pinfunction "2_2") (pintype "bidirectional+no_connect"))
    )
    (net (code "86") (name "unconnected-(J1-Pad3)") (class "Default")
      (node (ref "J1") (pin "3") (pinfunction "3_3") (pintype "bidirectional+no_connect"))
    )
    (net (code "87") (name "unconnected-(J1-PadMH1)") (class "Default")
      (node (ref "J1") (pin "MH1") (pinfunction "MH1_MH1") (pintype "bidirectional+no_connect"))
    )
    (net (code "88") (name "unconnected-(J1-PadMH2)") (class "Default")
      (node (ref "J1") (pin "MH2") (pinfunction "MH2_MH2") (pintype "bidirectional+no_connect"))
    )
    (net (code "89") (name "unconnected-(U1-A0-Pad2)") (class "Default")
      (node (ref "U1") (pin "2") (pinfunction "A0_2") (pintype "input+no_connect"))
    )
    (net (code "90") (name "unconnected-(U1-A1-Pad23)") (class "Default")
      (node (ref "U1") (pin "23") (pinfunction "A1_23") (pintype "input+no_connect"))
    )
    (net (code "91") (name "unconnected-(U1-A2-Pad21)") (class "Default")
      (node (ref "U1") (pin "21") (pinfunction "A2_21") (pintype "input+no_connect"))
    )
    (net (code "92") (name "unconnected-(U1-A3-Pad19)") (class "Default")
      (node (ref "U1") (pin "19") (pinfunction "A3_19") (pintype "input+no_connect"))
    )
    (net (code "93") (name "unconnected-(U1-A=B-Pad14)") (class "Default")
      (node (ref "U1") (pin "14") (pinfunction "A=B_14") (pintype "output+no_connect"))
    )
    (net (code "94") (name "unconnected-(U1-B0-Pad1)") (class "Default")
      (node (ref "U1") (pin "1") (pinfunction "B0_1") (pintype "input+no_connect"))
    )
    (net (code "95") (name "unconnected-(U1-B1-Pad22)") (class "Default")
      (node (ref "U1") (pin "22") (pinfunction "B1_22") (pintype "input+no_connect"))
    )
    (net (code "96") (name "unconnected-(U1-B2-Pad20)") (class "Default")
      (node (ref "U1") (pin "20") (pinfunction "B2_20") (pintype "input+no_connect"))
    )
    (net (code "97") (name "unconnected-(U1-B3-Pad18)") (class "Default")
      (node (ref "U1") (pin "18") (pinfunction "B3_18") (pintype "input+no_connect"))
    )
    (net (code "98") (name "unconnected-(U1-Cn+4-Pad16)") (class "Default")
      (node (ref "U1") (pin "16") (pinfunction "Cn+4_16") (pintype "output+no_connect"))
    )
    (net (code "99") (name "unconnected-(U1-Cn-Pad7)") (class "Default")
      (node (ref "U1") (pin "7") (pinfunction "Cn_7") (pintype "input+no_connect"))
    )
    (net (code "100") (name "unconnected-(U1-F0-Pad9)") (class "Default")
      (node (ref "U1") (pin "9") (pinfunction "F0_9") (pintype "output+no_connect"))
    )
    (net (code "101") (name "unconnected-(U1-F1-Pad10)") (class "Default")
      (node (ref "U1") (pin "10") (pinfunction "F1_10") (pintype "output+no_connect"))
    )
    (net (code "102") (name "unconnected-(U1-F2-Pad11)") (class "Default")
      (node (ref "U1") (pin "11") (pinfunction "F2_11") (pintype "output+no_connect"))
    )
    (net (code "103") (name "unconnected-(U1-F3-Pad13)") (class "Default")
      (node (ref "U1") (pin "13") (pinfunction "F3_13") (pintype "output+no_connect"))
    )
    (net (code "104") (name "unconnected-(U1-GND-Pad12)") (class "Default")
      (node (ref "U1") (pin "12") (pinfunction "GND_12") (pintype "bidirectional"))
    )
    (net (code "105") (name "unconnected-(U1-M-Pad8)") (class "Default")
      (node (ref "U1") (pin "8") (pinfunction "M_8") (pintype "input+no_connect"))
    )
    (net (code "106") (name "unconnected-(U1-S0-Pad6)") (class "Default")
      (node (ref "U1") (pin "6") (pinfunction "S0_6") (pintype "input+no_connect"))
    )
    (net (code "107") (name "unconnected-(U1-S1-Pad5)") (class "Default")
      (node (ref "U1") (pin "5") (pinfunction "S1_5") (pintype "input+no_connect"))
    )
    (net (code "108") (name "unconnected-(U1-S2-Pad4)") (class "Default")
      (node (ref "U1") (pin "4") (pinfunction "S2_4") (pintype "input+no_connect"))
    )
    (net (code "109") (name "unconnected-(U1-S3-Pad3)") (class "Default")
      (node (ref "U1") (pin "3") (pinfunction "S3_3") (pintype "input+no_connect"))
    )
    (net (code "110") (name "unconnected-(U1-VCC-Pad24)") (class "Default")
      (node (ref "U1") (pin "24") (pinfunction "VCC_24") (pintype "bidirectional"))
    )
    (net (code "111") (name "unconnected-(U1-X-Pad15)") (class "Default")
      (node (ref "U1") (pin "15") (pinfunction "X_15") (pintype "output+no_connect"))
    )
    (net (code "112") (name "unconnected-(U1-Y-Pad17)") (class "Default")
      (node (ref "U1") (pin "17") (pinfunction "Y_17") (pintype "output+no_connect"))
    )
    (net (code "113") (name "unconnected-(U2-A0-Pad2)") (class "Default")
      (node (ref "U2") (pin "2") (pinfunction "A0_2") (pintype "input+no_connect"))
    )
    (net (code "114") (name "unconnected-(U2-A1-Pad23)") (class "Default")
      (node (ref "U2") (pin "23") (pinfunction "A1_23") (pintype "input+no_connect"))
    )
    (net (code "115") (name "unconnected-(U2-A2-Pad21)") (class "Default")
      (node (ref "U2") (pin "21") (pinfunction "A2_21") (pintype "input+no_connect"))
    )
    (net (code "116") (name "unconnected-(U2-A3-Pad19)") (class "Default")
      (node (ref "U2") (pin "19") (pinfunction "A3_19") (pintype "input+no_connect"))
    )
    (net (code "117") (name "unconnected-(U2-A=B-Pad14)") (class "Default")
      (node (ref "U2") (pin "14") (pinfunction "A=B_14") (pintype "output+no_connect"))
    )
    (net (code "118") (name "unconnected-(U2-B0-Pad1)") (class "Default")
      (node (ref "U2") (pin "1") (pinfunction "B0_1") (pintype "input+no_connect"))
    )
    (net (code "119") (name "unconnected-(U2-B1-Pad22)") (class "Default")
      (node (ref "U2") (pin "22") (pinfunction "B1_22") (pintype "input+no_connect"))
    )
    (net (code "120") (name "unconnected-(U2-B2-Pad20)") (class "Default")
      (node (ref "U2") (pin "20") (pinfunction "B2_20") (pintype "input+no_connect"))
    )
    (net (code "121") (name "unconnected-(U2-B3-Pad18)") (class "Default")
      (node (ref "U2") (pin "18") (pinfunction "B3_18") (pintype "input+no_connect"))
    )
    (net (code "122") (name "unconnected-(U2-Cn+4-Pad16)") (class "Default")
      (node (ref "U2") (pin "16") (pinfunction "Cn+4_16") (pintype "output+no_connect"))
    )
    (net (code "123") (name "unconnected-(U2-Cn-Pad7)") (class "Default")
      (node (ref "U2") (pin "7") (pinfunction "Cn_7") (pintype "input+no_connect"))
    )
    (net (code "124") (name "unconnected-(U2-F0-Pad9)") (class "Default")
      (node (ref "U2") (pin "9") (pinfunction "F0_9") (pintype "output+no_connect"))
    )
    (net (code "125") (name "unconnected-(U2-F1-Pad10)") (class "Default")
      (node (ref "U2") (pin "10") (pinfunction "F1_10") (pintype "output+no_connect"))
    )
    (net (code "126") (name "unconnected-(U2-F2-Pad11)") (class "Default")
      (node (ref "U2") (pin "11") (pinfunction "F2_11") (pintype "output+no_connect"))
    )
    (net (code "127") (name "unconnected-(U2-F3-Pad13)") (class "Default")
      (node (ref "U2") (pin "13") (pinfunction "F3_13") (pintype "output+no_connect"))
    )
    (net (code "128") (name "unconnected-(U2-GND-Pad12)") (class "Default")
      (node (ref "U2") (pin "12") (pinfunction "GND_12") (pintype "bidirectional"))
    )
    (net (code "129") (name "unconnected-(U2-M-Pad8)") (class "Default")
      (node (ref "U2") (pin "8") (pinfunction "M_8") (pintype "input+no_connect"))
    )
    (net (code "130") (name "unconnected-(U2-S0-Pad6)") (class "Default")
      (node (ref "U2") (pin "6") (pinfunction "S0_6") (pintype "input+no_connect"))
    )
    (net (code "131") (name "unconnected-(U2-S1-Pad5)") (class "Default")
      (node (ref "U2") (pin "5") (pinfunction "S1_5") (pintype "input+no_connect"))
    )
    (net (code "132") (name "unconnected-(U2-S2-Pad4)") (class "Default")
      (node (ref "U2") (pin "4") (pinfunction "S2_4") (pintype "input+no_connect"))
    )
    (net (code "133") (name "unconnected-(U2-S3-Pad3)") (class "Default")
      (node (ref "U2") (pin "3") (pinfunction "S3_3") (pintype "input+no_connect"))
    )
    (net (code "134") (name "unconnected-(U2-VCC-Pad24)") (class "Default")
      (node (ref "U2") (pin "24") (pinfunction "VCC_24") (pintype "bidirectional"))
    )
    (net (code "135") (name "unconnected-(U2-X-Pad15)") (class "Default")
      (node (ref "U2") (pin "15") (pinfunction "X_15") (pintype "output+no_connect"))
    )
    (net (code "136") (name "unconnected-(U2-Y-Pad17)") (class "Default")
      (node (ref "U2") (pin "17") (pinfunction "Y_17") (pintype "output+no_connect"))
    )
    (net (code "137") (name "unconnected-(U3-A0-Pad2)") (class "Default")
      (node (ref "U3") (pin "2") (pinfunction "A0_2") (pintype "input+no_connect"))
    )
    (net (code "138") (name "unconnected-(U3-A1-Pad23)") (class "Default")
      (node (ref "U3") (pin "23") (pinfunction "A1_23") (pintype "input+no_connect"))
    )
    (net (code "139") (name "unconnected-(U3-A2-Pad21)") (class "Default")
      (node (ref "U3") (pin "21") (pinfunction "A2_21") (pintype "input+no_connect"))
    )
    (net (code "140") (name "unconnected-(U3-A3-Pad19)") (class "Default")
      (node (ref "U3") (pin "19") (pinfunction "A3_19") (pintype "input+no_connect"))
    )
    (net (code "141") (name "unconnected-(U3-A=B-Pad14)") (class "Default")
      (node (ref "U3") (pin "14") (pinfunction "A=B_14") (pintype "output+no_connect"))
    )
    (net (code "142") (name "unconnected-(U3-B0-Pad1)") (class "Default")
      (node (ref "U3") (pin "1") (pinfunction "B0_1") (pintype "input+no_connect"))
    )
    (net (code "143") (name "unconnected-(U3-B1-Pad22)") (class "Default")
      (node (ref "U3") (pin "22") (pinfunction "B1_22") (pintype "input+no_connect"))
    )
    (net (code "144") (name "unconnected-(U3-B2-Pad20)") (class "Default")
      (node (ref "U3") (pin "20") (pinfunction "B2_20") (pintype "input+no_connect"))
    )
    (net (code "145") (name "unconnected-(U3-B3-Pad18)") (class "Default")
      (node (ref "U3") (pin "18") (pinfunction "B3_18") (pintype "input+no_connect"))
    )
    (net (code "146") (name "unconnected-(U3-Cn+4-Pad16)") (class "Default")
      (node (ref "U3") (pin "16") (pinfunction "Cn+4_16") (pintype "output+no_connect"))
    )
    (net (code "147") (name "unconnected-(U3-Cn-Pad7)") (class "Default")
      (node (ref "U3") (pin "7") (pinfunction "Cn_7") (pintype "input+no_connect"))
    )
    (net (code "148") (name "unconnected-(U3-F0-Pad9)") (class "Default")
      (node (ref "U3") (pin "9") (pinfunction "F0_9") (pintype "output+no_connect"))
    )
    (net (code "149") (name "unconnected-(U3-F1-Pad10)") (class "Default")
      (node (ref "U3") (pin "10") (pinfunction "F1_10") (pintype "output+no_connect"))
    )
    (net (code "150") (name "unconnected-(U3-F2-Pad11)") (class "Default")
      (node (ref "U3") (pin "11") (pinfunction "F2_11") (pintype "output+no_connect"))
    )
    (net (code "151") (name "unconnected-(U3-F3-Pad13)") (class "Default")
      (node (ref "U3") (pin "13") (pinfunction "F3_13") (pintype "output+no_connect"))
    )
    (net (code "152") (name "unconnected-(U3-GND-Pad12)") (class "Default")
      (node (ref "U3") (pin "12") (pinfunction "GND_12") (pintype "bidirectional"))
    )
    (net (code "153") (name "unconnected-(U3-M-Pad8)") (class "Default")
      (node (ref "U3") (pin "8") (pinfunction "M_8") (pintype "input+no_connect"))
    )
    (net (code "154") (name "unconnected-(U3-S0-Pad6)") (class "Default")
      (node (ref "U3") (pin "6") (pinfunction "S0_6") (pintype "input+no_connect"))
    )
    (net (code "155") (name "unconnected-(U3-S1-Pad5)") (class "Default")
      (node (ref "U3") (pin "5") (pinfunction "S1_5") (pintype "input+no_connect"))
    )
    (net (code "156") (name "unconnected-(U3-S2-Pad4)") (class "Default")
      (node (ref "U3") (pin "4") (pinfunction "S2_4") (pintype "input+no_connect"))
    )
    (net (code "157") (name "unconnected-(U3-S3-Pad3)") (class "Default")
      (node (ref "U3") (pin "3") (pinfunction "S3_3") (pintype "input+no_connect"))
    )
    (net (code "158") (name "unconnected-(U3-VCC-Pad24)") (class "Default")
      (node (ref "U3") (pin "24") (pinfunction "VCC_24") (pintype "bidirectional"))
    )
    (net (code "159") (name "unconnected-(U3-X-Pad15)") (class "Default")
      (node (ref "U3") (pin "15") (pinfunction "X_15") (pintype "output+no_connect"))
    )
    (net (code "160") (name "unconnected-(U3-Y-Pad17)") (class "Default")
      (node (ref "U3") (pin "17") (pinfunction "Y_17") (pintype "output+no_connect"))
    )
    (net (code "161") (name "unconnected-(U4-A0-Pad2)") (class "Default")
      (node (ref "U4") (pin "2") (pinfunction "A0_2") (pintype "input+no_connect"))
    )
    (net (code "162") (name "unconnected-(U4-A1-Pad23)") (class "Default")
      (node (ref "U4") (pin "23") (pinfunction "A1_23") (pintype "input+no_connect"))
    )
    (net (code "163") (name "unconnected-(U4-A2-Pad21)") (class "Default")
      (node (ref "U4") (pin "21") (pinfunction "A2_21") (pintype "input+no_connect"))
    )
    (net (code "164") (name "unconnected-(U4-A3-Pad19)") (class "Default")
      (node (ref "U4") (pin "19") (pinfunction "A3_19") (pintype "input+no_connect"))
    )
    (net (code "165") (name "unconnected-(U4-A=B-Pad14)") (class "Default")
      (node (ref "U4") (pin "14") (pinfunction "A=B_14") (pintype "output+no_connect"))
    )
    (net (code "166") (name "unconnected-(U4-B0-Pad1)") (class "Default")
      (node (ref "U4") (pin "1") (pinfunction "B0_1") (pintype "input+no_connect"))
    )
    (net (code "167") (name "unconnected-(U4-B1-Pad22)") (class "Default")
      (node (ref "U4") (pin "22") (pinfunction "B1_22") (pintype "input+no_connect"))
    )
    (net (code "168") (name "unconnected-(U4-B2-Pad20)") (class "Default")
      (node (ref "U4") (pin "20") (pinfunction "B2_20") (pintype "input+no_connect"))
    )
    (net (code "169") (name "unconnected-(U4-B3-Pad18)") (class "Default")
      (node (ref "U4") (pin "18") (pinfunction "B3_18") (pintype "input+no_connect"))
    )
    (net (code "170") (name "unconnected-(U4-Cn+4-Pad16)") (class "Default")
      (node (ref "U4") (pin "16") (pinfunction "Cn+4_16") (pintype "output+no_connect"))
    )
    (net (code "171") (name "unconnected-(U4-Cn-Pad7)") (class "Default")
      (node (ref "U4") (pin "7") (pinfunction "Cn_7") (pintype "input+no_connect"))
    )
    (net (code "172") (name "unconnected-(U4-F0-Pad9)") (class "Default")
      (node (ref "U4") (pin "9") (pinfunction "F0_9") (pintype "output+no_connect"))
    )
    (net (code "173") (name "unconnected-(U4-F1-Pad10)") (class "Default")
      (node (ref "U4") (pin "10") (pinfunction "F1_10") (pintype "output+no_connect"))
    )
    (net (code "174") (name "unconnected-(U4-F2-Pad11)") (class "Default")
      (node (ref "U4") (pin "11") (pinfunction "F2_11") (pintype "output+no_connect"))
    )
    (net (code "175") (name "unconnected-(U4-F3-Pad13)") (class "Default")
      (node (ref "U4") (pin "13") (pinfunction "F3_13") (pintype "output+no_connect"))
    )
    (net (code "176") (name "unconnected-(U4-GND-Pad12)") (class "Default")
      (node (ref "U4") (pin "12") (pinfunction "GND_12") (pintype "bidirectional"))
    )
    (net (code "177") (name "unconnected-(U4-M-Pad8)") (class "Default")
      (node (ref "U4") (pin "8") (pinfunction "M_8") (pintype "input+no_connect"))
    )
    (net (code "178") (name "unconnected-(U4-S0-Pad6)") (class "Default")
      (node (ref "U4") (pin "6") (pinfunction "S0_6") (pintype "input+no_connect"))
    )
    (net (code "179") (name "unconnected-(U4-S1-Pad5)") (class "Default")
      (node (ref "U4") (pin "5") (pinfunction "S1_5") (pintype "input+no_connect"))
    )
    (net (code "180") (name "unconnected-(U4-S2-Pad4)") (class "Default")
      (node (ref "U4") (pin "4") (pinfunction "S2_4") (pintype "input+no_connect"))
    )
    (net (code "181") (name "unconnected-(U4-S3-Pad3)") (class "Default")
      (node (ref "U4") (pin "3") (pinfunction "S3_3") (pintype "input+no_connect"))
    )
    (net (code "182") (name "unconnected-(U4-VCC-Pad24)") (class "Default")
      (node (ref "U4") (pin "24") (pinfunction "VCC_24") (pintype "bidirectional"))
    )
    (net (code "183") (name "unconnected-(U4-X-Pad15)") (class "Default")
      (node (ref "U4") (pin "15") (pinfunction "X_15") (pintype "output+no_connect"))
    )
    (net (code "184") (name "unconnected-(U4-Y-Pad17)") (class "Default")
      (node (ref "U4") (pin "17") (pinfunction "Y_17") (pintype "output+no_connect"))
    )
    (net (code "185") (name "{slash}EN") (class "Default")
      (node (ref "H5") (pin "1") (pinfunction "1_1") (pintype "unspecified"))
      (node (ref "U5") (pin "1") (pinfunction "CLKEN#_1") (pintype "unspecified"))
      (node (ref "U6") (pin "1") (pinfunction "CLKEN#_1") (pintype "unspecified"))
    )
    (net (code "186") (name "{slash}OE") (class "Default")
      (node (ref "H5") (pin "2") (pinfunction "2_2") (pintype "unspecified"))
      (node (ref "U7") (pin "19") (pinfunction "OE_19") (pintype "unspecified"))
      (node (ref "U8") (pin "19") (pinfunction "OE_19") (pintype "unspecified"))
    )
  )
)
